# SC01_ProtoBoard_V0_1.net
KiCad netlist of a schematic drawn in EAGLE
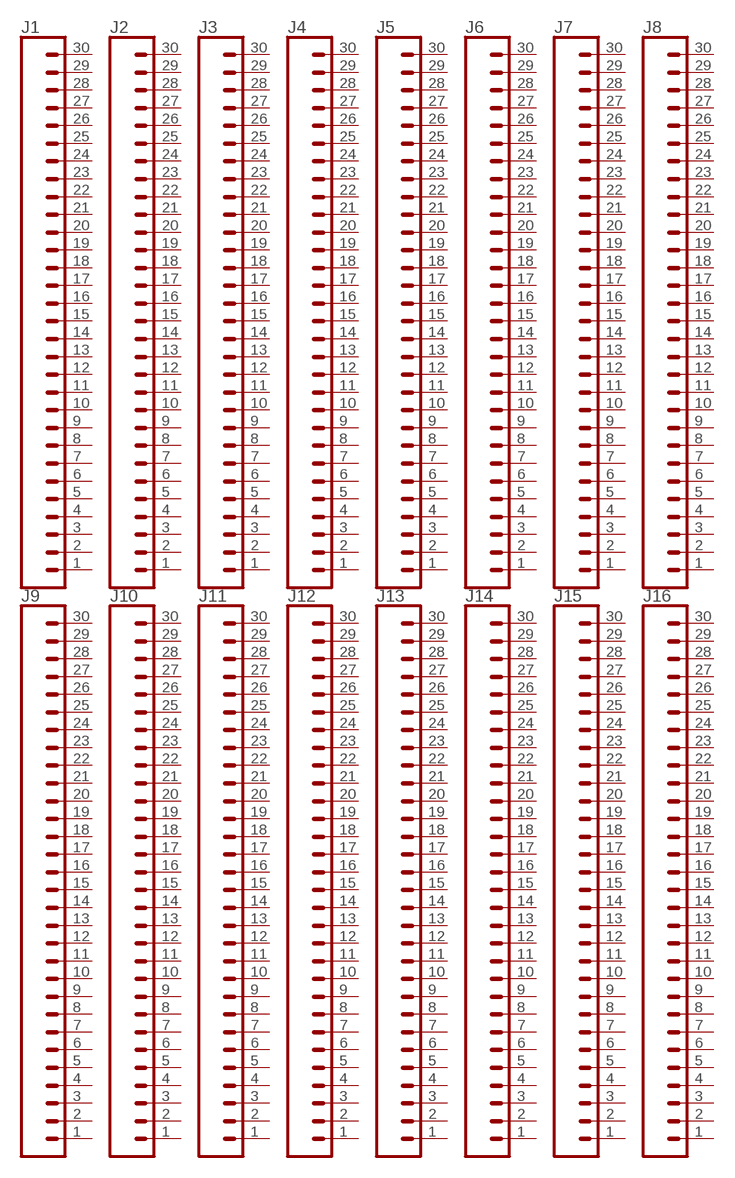
[diagram p0: schematic, sheet 1]
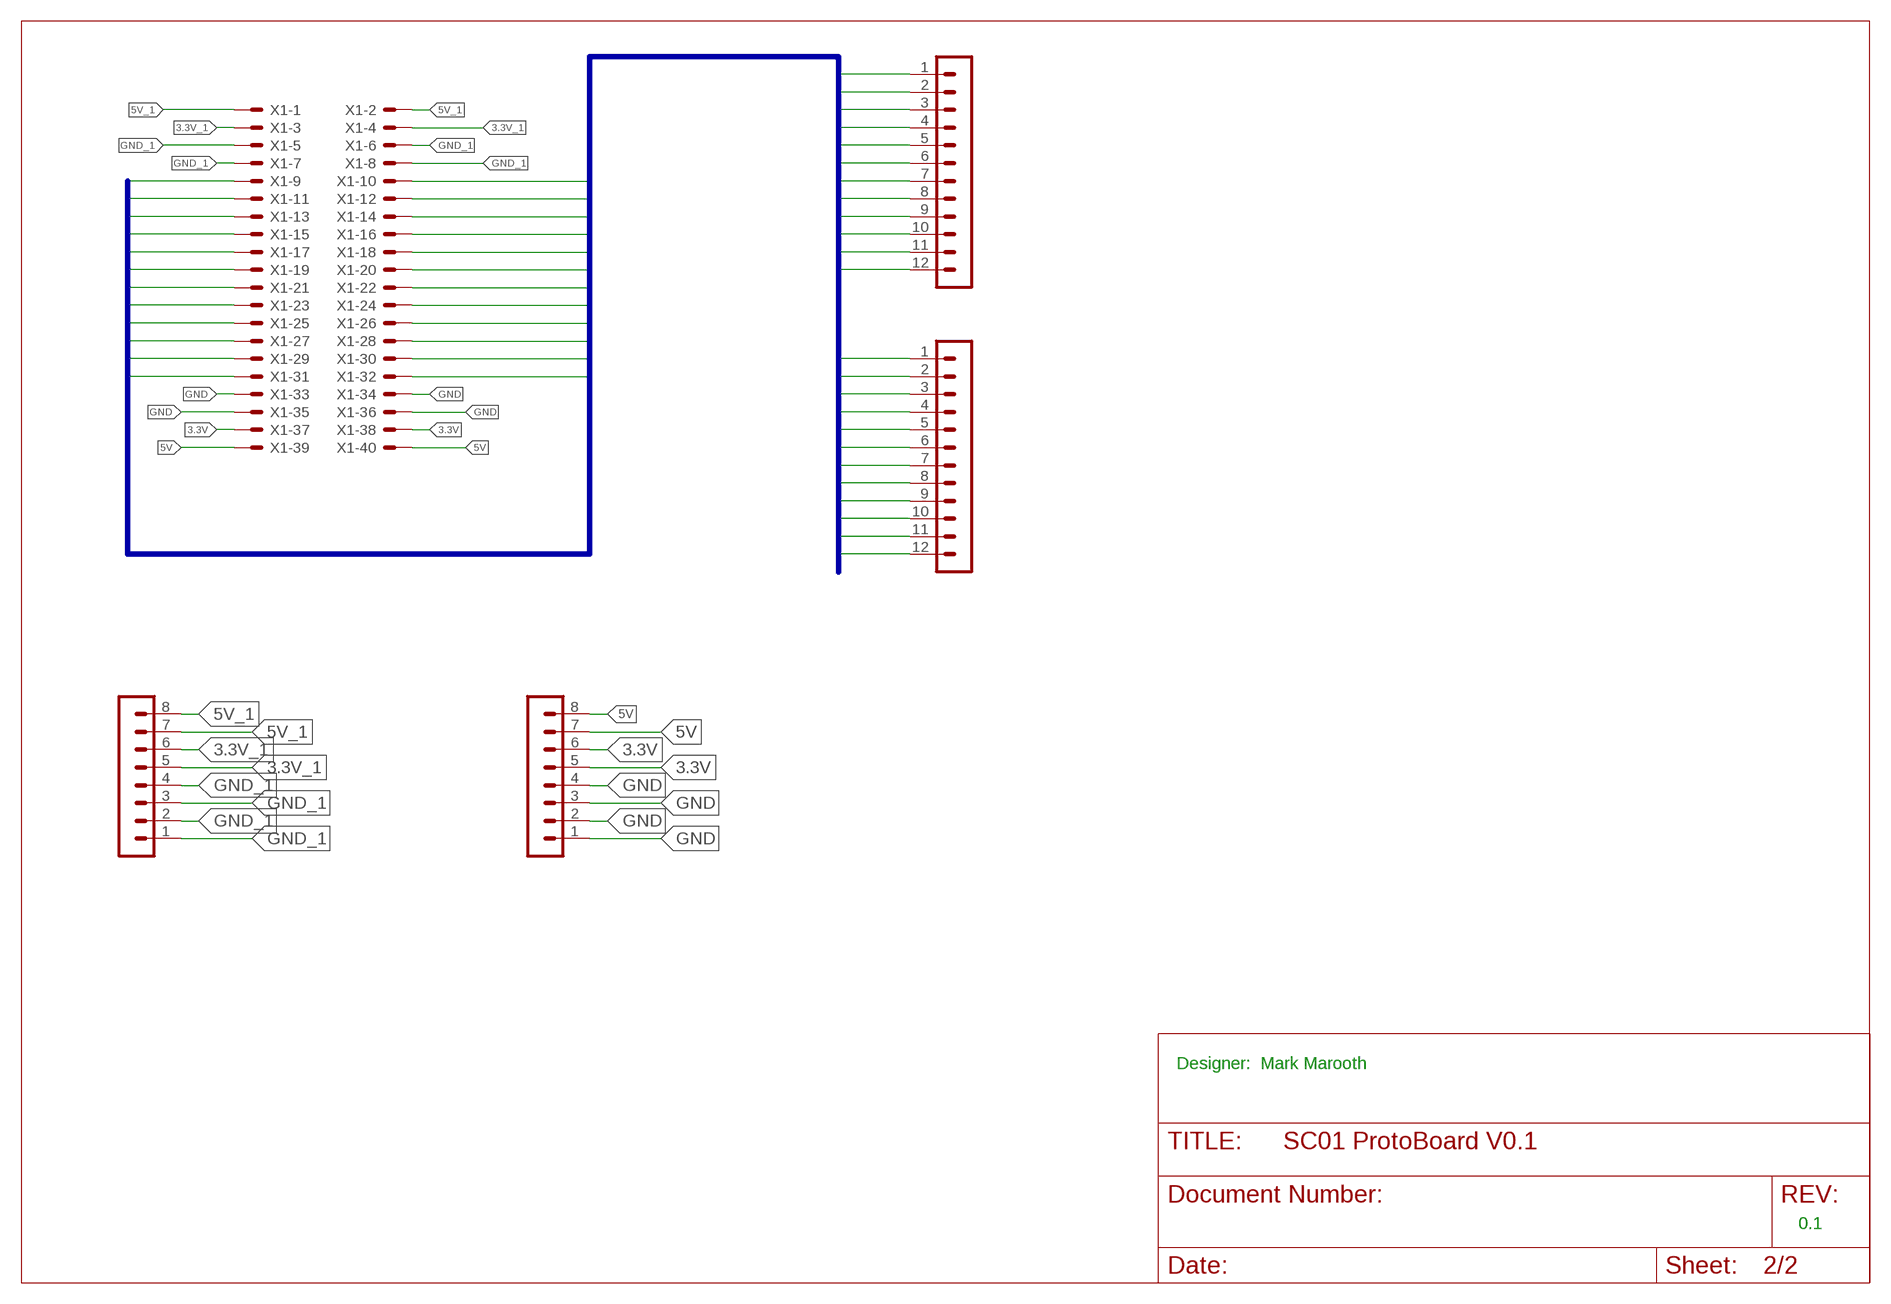
[diagram p1: schematic, sheet 2]

(export (version "E")
  (design (tool "Eeschema 10.0.6"))
  (components
    (comp (ref "J1")
      (value "CONN_30NO_SILK")
      (footprint "eagle-import:1X30_NO_SILK")
      (libsource (lib "eagle-import") (part "CONN_30NO_SILK"))
    )
    (comp (ref "J2")
      (value "CONN_30NO_SILK")
      (footprint "eagle-import:1X30_NO_SILK")
      (libsource (lib "eagle-import") (part "CONN_30NO_SILK"))
    )
    (comp (ref "J3")
      (value "CONN_30NO_SILK")
      (footprint "eagle-import:1X30_NO_SILK")
      (libsource (lib "eagle-import") (part "CONN_30NO_SILK"))
    )
    (comp (ref "J4")
      (value "CONN_30NO_SILK")
      (footprint "eagle-import:1X30_NO_SILK")
      (libsource (lib "eagle-import") (part "CONN_30NO_SILK"))
    )
    (comp (ref "J5")
      (value "CONN_30NO_SILK")
      (footprint "eagle-import:1X30_NO_SILK")
      (libsource (lib "eagle-import") (part "CONN_30NO_SILK"))
    )
    (comp (ref "J6")
      (value "CONN_30NO_SILK")
      (footprint "eagle-import:1X30_NO_SILK")
      (libsource (lib "eagle-import") (part "CONN_30NO_SILK"))
    )
    (comp (ref "J7")
      (value "CONN_30NO_SILK")
      (footprint "eagle-import:1X30_NO_SILK")
      (libsource (lib "eagle-import") (part "CONN_30NO_SILK"))
    )
    (comp (ref "J8")
      (value "CONN_30NO_SILK")
      (footprint "eagle-import:1X30_NO_SILK")
      (libsource (lib "eagle-import") (part "CONN_30NO_SILK"))
    )
    (comp (ref "J9")
      (value "CONN_30NO_SILK")
      (footprint "eagle-import:1X30_NO_SILK")
      (libsource (lib "eagle-import") (part "CONN_30NO_SILK"))
    )
    (comp (ref "J10")
      (value "CONN_30NO_SILK")
      (footprint "eagle-import:1X30_NO_SILK")
      (libsource (lib "eagle-import") (part "CONN_30NO_SILK"))
    )
    (comp (ref "J11")
      (value "CONN_30NO_SILK")
      (footprint "eagle-import:1X30_NO_SILK")
      (libsource (lib "eagle-import") (part "CONN_30NO_SILK"))
    )
    (comp (ref "J12")
      (value "CONN_30NO_SILK")
      (footprint "eagle-import:1X30_NO_SILK")
      (libsource (lib "eagle-import") (part "CONN_30NO_SILK"))
    )
    (comp (ref "J13")
      (value "CONN_30NO_SILK")
      (footprint "eagle-import:1X30_NO_SILK")
      (libsource (lib "eagle-import") (part "CONN_30NO_SILK"))
    )
    (comp (ref "J14")
      (value "CONN_30NO_SILK")
      (footprint "eagle-import:1X30_NO_SILK")
      (libsource (lib "eagle-import") (part "CONN_30NO_SILK"))
    )
    (comp (ref "J15")
      (value "CONN_30NO_SILK")
      (footprint "eagle-import:1X30_NO_SILK")
      (libsource (lib "eagle-import") (part "CONN_30NO_SILK"))
    )
    (comp (ref "J16")
      (value "CONN_30NO_SILK")
      (footprint "eagle-import:1X30_NO_SILK")
      (libsource (lib "eagle-import") (part "CONN_30NO_SILK"))
    )
    (comp (ref "HDR1")
      (value "MA12-1")
      (footprint "eagle-import:MA12-1")
      (libsource (lib "eagle-import") (part "MA12-1"))
    )
    (comp (ref "HDR2")
      (value "MA12-1")
      (footprint "eagle-import:MA12-1")
      (libsource (lib "eagle-import") (part "MA12-1"))
    )
    (comp (ref "HDR3")
      (value "MA08-1")
      (footprint "eagle-import:MA08-1")
      (libsource (lib "eagle-import") (part "MA08-1"))
    )
    (comp (ref "HDR4")
      (value "MA08-1")
      (footprint "eagle-import:MA08-1")
      (libsource (lib "eagle-import") (part "MA08-1"))
    )
    (comp (ref "X1")
      (value "87758-4016")
      (footprint "eagle-import:87758-4016")
      (libsource (lib "eagle-import") (part "87758-4016"))
    )
  )
  (nets
    (net (code "1") (name "3.3V") (class "Default")
      (node (ref "HDR4") (pin "5") (pinfunction "5_5") (pintype "passive"))
      (node (ref "HDR4") (pin "6") (pinfunction "6_6") (pintype "passive"))
      (node (ref "X1") (pin "37") (pinfunction "S_37") (pintype "passive"))
      (node (ref "X1") (pin "38") (pinfunction "S_38") (pintype "passive"))
    )
    (net (code "2") (name "3.3V_1") (class "Default")
      (node (ref "HDR3") (pin "5") (pinfunction "5_5") (pintype "passive"))
      (node (ref "HDR3") (pin "6") (pinfunction "6_6") (pintype "passive"))
      (node (ref "X1") (pin "3") (pinfunction "S_3") (pintype "passive"))
      (node (ref "X1") (pin "4") (pinfunction "S_4") (pintype "passive"))
    )
    (net (code "3") (name "5V") (class "Default")
      (node (ref "HDR4") (pin "7") (pinfunction "7_7") (pintype "passive"))
      (node (ref "HDR4") (pin "8") (pinfunction "8_8") (pintype "passive"))
      (node (ref "X1") (pin "39") (pinfunction "S_39") (pintype "passive"))
      (node (ref "X1") (pin "40") (pinfunction "S_40") (pintype "passive"))
    )
    (net (code "4") (name "5V_1") (class "Default")
      (node (ref "HDR3") (pin "7") (pinfunction "7_7") (pintype "passive"))
      (node (ref "HDR3") (pin "8") (pinfunction "8_8") (pintype "passive"))
      (node (ref "X1") (pin "1") (pinfunction "S_1") (pintype "passive"))
      (node (ref "X1") (pin "2") (pinfunction "S_2") (pintype "passive"))
    )
    (net (code "5") (name "GND") (class "Default")
      (node (ref "HDR4") (pin "1") (pinfunction "1_1") (pintype "passive"))
      (node (ref "HDR4") (pin "2") (pinfunction "2_2") (pintype "passive"))
      (node (ref "HDR4") (pin "3") (pinfunction "3_3") (pintype "passive"))
      (node (ref "HDR4") (pin "4") (pinfunction "4_4") (pintype "passive"))
      (node (ref "X1") (pin "33") (pinfunction "S_33") (pintype "passive"))
      (node (ref "X1") (pin "34") (pinfunction "S_34") (pintype "passive"))
      (node (ref "X1") (pin "35") (pinfunction "S_35") (pintype "passive"))
      (node (ref "X1") (pin "36") (pinfunction "S_36") (pintype "passive"))
    )
    (net (code "6") (name "GND_1") (class "Default")
      (node (ref "HDR3") (pin "1") (pinfunction "1_1") (pintype "passive"))
      (node (ref "HDR3") (pin "2") (pinfunction "2_2") (pintype "passive"))
      (node (ref "HDR3") (pin "3") (pinfunction "3_3") (pintype "passive"))
      (node (ref "HDR3") (pin "4") (pinfunction "4_4") (pintype "passive"))
      (node (ref "X1") (pin "5") (pinfunction "S_5") (pintype "passive"))
      (node (ref "X1") (pin "6") (pinfunction "S_6") (pintype "passive"))
      (node (ref "X1") (pin "7") (pinfunction "S_7") (pintype "passive"))
      (node (ref "X1") (pin "8") (pinfunction "S_8") (pintype "passive"))
    )
    (net (code "7") (name "PHEADER9") (class "Default")
      (node (ref "HDR1") (pin "1") (pinfunction "1_1") (pintype "passive"))
      (node (ref "X1") (pin "9") (pinfunction "S_9") (pintype "passive"))
    )
    (net (code "8") (name "PHEADER10") (class "Default")
      (node (ref "HDR1") (pin "2") (pinfunction "2_2") (pintype "passive"))
      (node (ref "X1") (pin "10") (pinfunction "S_10") (pintype "passive"))
    )
    (net (code "9") (name "PHEADER11") (class "Default")
      (node (ref "HDR1") (pin "3") (pinfunction "3_3") (pintype "passive"))
      (node (ref "X1") (pin "11") (pinfunction "S_11") (pintype "passive"))
    )
    (net (code "10") (name "PHEADER12") (class "Default")
      (node (ref "HDR1") (pin "4") (pinfunction "4_4") (pintype "passive"))
      (node (ref "X1") (pin "12") (pinfunction "S_12") (pintype "passive"))
    )
    (net (code "11") (name "PHEADER13") (class "Default")
      (node (ref "HDR1") (pin "5") (pinfunction "5_5") (pintype "passive"))
      (node (ref "X1") (pin "13") (pinfunction "S_13") (pintype "passive"))
    )
    (net (code "12") (name "PHEADER14") (class "Default")
      (node (ref "HDR1") (pin "6") (pinfunction "6_6") (pintype "passive"))
      (node (ref "X1") (pin "14") (pinfunction "S_14") (pintype "passive"))
    )
    (net (code "13") (name "PHEADER15") (class "Default")
      (node (ref "HDR1") (pin "7") (pinfunction "7_7") (pintype "passive"))
      (node (ref "X1") (pin "15") (pinfunction "S_15") (pintype "passive"))
    )
    (net (code "14") (name "PHEADER16") (class "Default")
      (node (ref "HDR1") (pin "8") (pinfunction "8_8") (pintype "passive"))
      (node (ref "X1") (pin "16") (pinfunction "S_16") (pintype "passive"))
    )
    (net (code "15") (name "PHEADER17") (class "Default")
      (node (ref "HDR1") (pin "9") (pinfunction "9_9") (pintype "passive"))
      (node (ref "X1") (pin "17") (pinfunction "S_17") (pintype "passive"))
    )
    (net (code "16") (name "PHEADER18") (class "Default")
      (node (ref "HDR1") (pin "10") (pinfunction "10_10") (pintype "passive"))
      (node (ref "X1") (pin "18") (pinfunction "S_18") (pintype "passive"))
    )
    (net (code "17") (name "PHEADER19") (class "Default")
      (node (ref "HDR1") (pin "11") (pinfunction "11_11") (pintype "passive"))
      (node (ref "X1") (pin "19") (pinfunction "S_19") (pintype "passive"))
    )
    (net (code "18") (name "PHEADER20") (class "Default")
      (node (ref "HDR1") (pin "12") (pinfunction "12_12") (pintype "passive"))
      (node (ref "X1") (pin "20") (pinfunction "S_20") (pintype "passive"))
    )
    (net (code "19") (name "PHEADER21") (class "Default")
      (node (ref "HDR2") (pin "1") (pinfunction "1_1") (pintype "passive"))
      (node (ref "X1") (pin "21") (pinfunction "S_21") (pintype "passive"))
    )
    (net (code "20") (name "PHEADER22") (class "Default")
      (node (ref "HDR2") (pin "2") (pinfunction "2_2") (pintype "passive"))
      (node (ref "X1") (pin "22") (pinfunction "S_22") (pintype "passive"))
    )
    (net (code "21") (name "PHEADER23") (class "Default")
      (node (ref "HDR2") (pin "3") (pinfunction "3_3") (pintype "passive"))
      (node (ref "X1") (pin "23") (pinfunction "S_23") (pintype "passive"))
    )
    (net (code "22") (name "PHEADER24") (class "Default")
      (node (ref "HDR2") (pin "4") (pinfunction "4_4") (pintype "passive"))
      (node (ref "X1") (pin "24") (pinfunction "S_24") (pintype "passive"))
    )
    (net (code "23") (name "PHEADER25") (class "Default")
      (node (ref "HDR2") (pin "5") (pinfunction "5_5") (pintype "passive"))
      (node (ref "X1") (pin "25") (pinfunction "S_25") (pintype "passive"))
    )
    (net (code "24") (name "PHEADER26") (class "Default")
      (node (ref "HDR2") (pin "6") (pinfunction "6_6") (pintype "passive"))
      (node (ref "X1") (pin "26") (pinfunction "S_26") (pintype "passive"))
    )
    (net (code "25") (name "PHEADER27") (class "Default")
      (node (ref "HDR2") (pin "7") (pinfunction "7_7") (pintype "passive"))
      (node (ref "X1") (pin "27") (pinfunction "S_27") (pintype "passive"))
    )
    (net (code "26") (name "PHEADER28") (class "Default")
      (node (ref "HDR2") (pin "8") (pinfunction "8_8") (pintype "passive"))
      (node (ref "X1") (pin "28") (pinfunction "S_28") (pintype "passive"))
    )
    (net (code "27") (name "PHEADER29") (class "Default")
      (node (ref "HDR2") (pin "9") (pinfunction "9_9") (pintype "passive"))
      (node (ref "X1") (pin "29") (pinfunction "S_29") (pintype "passive"))
    )
    (net (code "28") (name "PHEADER30") (class "Default")
      (node (ref "HDR2") (pin "10") (pinfunction "10_10") (pintype "passive"))
      (node (ref "X1") (pin "30") (pinfunction "S_30") (pintype "passive"))
    )
    (net (code "29") (name "PHEADER31") (class "Default")
      (node (ref "HDR2") (pin "11") (pinfunction "11_11") (pintype "passive"))
      (node (ref "X1") (pin "31") (pinfunction "S_31") (pintype "passive"))
    )
    (net (code "30") (name "PHEADER32") (class "Default")
      (node (ref "HDR2") (pin "12") (pinfunction "12_12") (pintype "passive"))
      (node (ref "X1") (pin "32") (pinfunction "S_32") (pintype "passive"))
    )
    (net (code "31") (name "unconnected-(J1-Pad1)") (class "Default")
      (node (ref "J1") (pin "1") (pinfunction "1_1") (pintype "passive"))
    )
    (net (code "32") (name "unconnected-(J1-Pad2)") (class "Default")
      (node (ref "J1") (pin "2") (pinfunction "2_2") (pintype "passive"))
    )
    (net (code "33") (name "unconnected-(J1-Pad3)") (class "Default")
      (node (ref "J1") (pin "3") (pinfunction "3_3") (pintype "passive"))
    )
    (net (code "34") (name "unconnected-(J1-Pad4)") (class "Default")
      (node (ref "J1") (pin "4") (pinfunction "4_4") (pintype "passive"))
    )
    (net (code "35") (name "unconnected-(J1-Pad5)") (class "Default")
      (node (ref "J1") (pin "5") (pinfunction "5_5") (pintype "passive"))
    )
    (net (code "36") (name "unconnected-(J1-Pad6)") (class "Default")
      (node (ref "J1") (pin "6") (pinfunction "6_6") (pintype "passive"))
    )
    (net (code "37") (name "unconnected-(J1-Pad7)") (class "Default")
      (node (ref "J1") (pin "7") (pinfunction "7_7") (pintype "passive"))
    )
    (net (code "38") (name "unconnected-(J1-Pad8)") (class "Default")
      (node (ref "J1") (pin "8") (pinfunction "8_8") (pintype "passive"))
    )
    (net (code "39") (name "unconnected-(J1-Pad9)") (class "Default")
      (node (ref "J1") (pin "9") (pinfunction "9_9") (pintype "passive"))
    )
    (net (code "40") (name "unconnected-(J1-Pad10)") (class "Default")
      (node (ref "J1") (pin "10") (pinfunction "10_10") (pintype "passive"))
    )
    (net (code "41") (name "unconnected-(J1-Pad11)") (class "Default")
      (node (ref "J1") (pin "11") (pinfunction "11_11") (pintype "passive"))
    )
    (net (code "42") (name "unconnected-(J1-Pad12)") (class "Default")
      (node (ref "J1") (pin "12") (pinfunction "12_12") (pintype "passive"))
    )
    (net (code "43") (name "unconnected-(J1-Pad13)") (class "Default")
      (node (ref "J1") (pin "13") (pinfunction "13_13") (pintype "passive"))
    )
    (net (code "44") (name "unconnected-(J1-Pad14)") (class "Default")
      (node (ref "J1") (pin "14") (pinfunction "14_14") (pintype "passive"))
    )
    (net (code "45") (name "unconnected-(J1-Pad15)") (class "Default")
      (node (ref "J1") (pin "15") (pinfunction "15_15") (pintype "passive"))
    )
    (net (code "46") (name "unconnected-(J1-Pad16)") (class "Default")
      (node (ref "J1") (pin "16") (pinfunction "16_16") (pintype "passive"))
    )
    (net (code "47") (name "unconnected-(J1-Pad17)") (class "Default")
      (node (ref "J1") (pin "17") (pinfunction "17_17") (pintype "passive"))
    )
    (net (code "48") (name "unconnected-(J1-Pad18)") (class "Default")
      (node (ref "J1") (pin "18") (pinfunction "18_18") (pintype "passive"))
    )
    (net (code "49") (name "unconnected-(J1-Pad19)") (class "Default")
      (node (ref "J1") (pin "19") (pinfunction "19_19") (pintype "passive"))
    )
    (net (code "50") (name "unconnected-(J1-Pad20)") (class "Default")
      (node (ref "J1") (pin "20") (pinfunction "20_20") (pintype "passive"))
    )
    (net (code "51") (name "unconnected-(J1-Pad21)") (class "Default")
      (node (ref "J1") (pin "21") (pinfunction "21_21") (pintype "passive"))
    )
    (net (code "52") (name "unconnected-(J1-Pad22)") (class "Default")
      (node (ref "J1") (pin "22") (pinfunction "22_22") (pintype "passive"))
    )
    (net (code "53") (name "unconnected-(J1-Pad23)") (class "Default")
      (node (ref "J1") (pin "23") (pinfunction "23_23") (pintype "passive"))
    )
    (net (code "54") (name "unconnected-(J1-Pad24)") (class "Default")
      (node (ref "J1") (pin "24") (pinfunction "24_24") (pintype "passive"))
    )
    (net (code "55") (name "unconnected-(J1-Pad25)") (class "Default")
      (node (ref "J1") (pin "25") (pinfunction "25_25") (pintype "passive"))
    )
    (net (code "56") (name "unconnected-(J1-Pad26)") (class "Default")
      (node (ref "J1") (pin "26") (pinfunction "26_26") (pintype "passive"))
    )
    (net (code "57") (name "unconnected-(J1-Pad27)") (class "Default")
      (node (ref "J1") (pin "27") (pinfunction "27_27") (pintype "passive"))
    )
    (net (code "58") (name "unconnected-(J1-Pad28)") (class "Default")
      (node (ref "J1") (pin "28") (pinfunction "28_28") (pintype "passive"))
    )
    (net (code "59") (name "unconnected-(J1-Pad29)") (class "Default")
      (node (ref "J1") (pin "29") (pinfunction "29_29") (pintype "passive"))
    )
    (net (code "60") (name "unconnected-(J1-Pad30)") (class "Default")
      (node (ref "J1") (pin "30") (pinfunction "30_30") (pintype "passive"))
    )
    (net (code "61") (name "unconnected-(J2-Pad1)") (class "Default")
      (node (ref "J2") (pin "1") (pinfunction "1_1") (pintype "passive"))
    )
    (net (code "62") (name "unconnected-(J2-Pad2)") (class "Default")
      (node (ref "J2") (pin "2") (pinfunction "2_2") (pintype "passive"))
    )
    (net (code "63") (name "unconnected-(J2-Pad3)") (class "Default")
      (node (ref "J2") (pin "3") (pinfunction "3_3") (pintype "passive"))
    )
    (net (code "64") (name "unconnected-(J2-Pad4)") (class "Default")
      (node (ref "J2") (pin "4") (pinfunction "4_4") (pintype "passive"))
    )
    (net (code "65") (name "unconnected-(J2-Pad5)") (class "Default")
      (node (ref "J2") (pin "5") (pinfunction "5_5") (pintype "passive"))
    )
    (net (code "66") (name "unconnected-(J2-Pad6)") (class "Default")
      (node (ref "J2") (pin "6") (pinfunction "6_6") (pintype "passive"))
    )
    (net (code "67") (name "unconnected-(J2-Pad7)") (class "Default")
      (node (ref "J2") (pin "7") (pinfunction "7_7") (pintype "passive"))
    )
    (net (code "68") (name "unconnected-(J2-Pad8)") (class "Default")
      (node (ref "J2") (pin "8") (pinfunction "8_8") (pintype "passive"))
    )
    (net (code "69") (name "unconnected-(J2-Pad9)") (class "Default")
      (node (ref "J2") (pin "9") (pinfunction "9_9") (pintype "passive"))
    )
    (net (code "70") (name "unconnected-(J2-Pad10)") (class "Default")
      (node (ref "J2") (pin "10") (pinfunction "10_10") (pintype "passive"))
    )
    (net (code "71") (name "unconnected-(J2-Pad11)") (class "Default")
      (node (ref "J2") (pin "11") (pinfunction "11_11") (pintype "passive"))
    )
    (net (code "72") (name "unconnected-(J2-Pad12)") (class "Default")
      (node (ref "J2") (pin "12") (pinfunction "12_12") (pintype "passive"))
    )
    (net (code "73") (name "unconnected-(J2-Pad13)") (class "Default")
      (node (ref "J2") (pin "13") (pinfunction "13_13") (pintype "passive"))
    )
    (net (code "74") (name "unconnected-(J2-Pad14)") (class "Default")
      (node (ref "J2") (pin "14") (pinfunction "14_14") (pintype "passive"))
    )
    (net (code "75") (name "unconnected-(J2-Pad15)") (class "Default")
      (node (ref "J2") (pin "15") (pinfunction "15_15") (pintype "passive"))
    )
    (net (code "76") (name "unconnected-(J2-Pad16)") (class "Default")
      (node (ref "J2") (pin "16") (pinfunction "16_16") (pintype "passive"))
    )
    (net (code "77") (name "unconnected-(J2-Pad17)") (class "Default")
      (node (ref "J2") (pin "17") (pinfunction "17_17") (pintype "passive"))
    )
    (net (code "78") (name "unconnected-(J2-Pad18)") (class "Default")
      (node (ref "J2") (pin "18") (pinfunction "18_18") (pintype "passive"))
    )
    (net (code "79") (name "unconnected-(J2-Pad19)") (class "Default")
      (node (ref "J2") (pin "19") (pinfunction "19_19") (pintype "passive"))
    )
    (net (code "80") (name "unconnected-(J2-Pad20)") (class "Default")
      (node (ref "J2") (pin "20") (pinfunction "20_20") (pintype "passive"))
    )
    (net (code "81") (name "unconnected-(J2-Pad21)") (class "Default")
      (node (ref "J2") (pin "21") (pinfunction "21_21") (pintype "passive"))
    )
    (net (code "82") (name "unconnected-(J2-Pad22)") (class "Default")
      (node (ref "J2") (pin "22") (pinfunction "22_22") (pintype "passive"))
    )
    (net (code "83") (name "unconnected-(J2-Pad23)") (class "Default")
      (node (ref "J2") (pin "23") (pinfunction "23_23") (pintype "passive"))
    )
    (net (code "84") (name "unconnected-(J2-Pad24)") (class "Default")
      (node (ref "J2") (pin "24") (pinfunction "24_24") (pintype "passive"))
    )
    (net (code "85") (name "unconnected-(J2-Pad25)") (class "Default")
      (node (ref "J2") (pin "25") (pinfunction "25_25") (pintype "passive"))
    )
    (net (code "86") (name "unconnected-(J2-Pad26)") (class "Default")
      (node (ref "J2") (pin "26") (pinfunction "26_26") (pintype "passive"))
    )
    (net (code "87") (name "unconnected-(J2-Pad27)") (class "Default")
      (node (ref "J2") (pin "27") (pinfunction "27_27") (pintype "passive"))
    )
    (net (code "88") (name "unconnected-(J2-Pad28)") (class "Default")
      (node (ref "J2") (pin "28") (pinfunction "28_28") (pintype "passive"))
    )
    (net (code "89") (name "unconnected-(J2-Pad29)") (class "Default")
      (node (ref "J2") (pin "29") (pinfunction "29_29") (pintype "passive"))
    )
    (net (code "90") (name "unconnected-(J2-Pad30)") (class "Default")
      (node (ref "J2") (pin "30") (pinfunction "30_30") (pintype "passive"))
    )
    (net (code "91") (name "unconnected-(J3-Pad1)") (class "Default")
      (node (ref "J3") (pin "1") (pinfunction "1_1") (pintype "passive"))
    )
    (net (code "92") (name "unconnected-(J3-Pad2)") (class "Default")
      (node (ref "J3") (pin "2") (pinfunction "2_2") (pintype "passive"))
    )
    (net (code "93") (name "unconnected-(J3-Pad3)") (class "Default")
      (node (ref "J3") (pin "3") (pinfunction "3_3") (pintype "passive"))
    )
    (net (code "94") (name "unconnected-(J3-Pad4)") (class "Default")
      (node (ref "J3") (pin "4") (pinfunction "4_4") (pintype "passive"))
    )
    (net (code "95") (name "unconnected-(J3-Pad5)") (class "Default")
      (node (ref "J3") (pin "5") (pinfunction "5_5") (pintype "passive"))
    )
    (net (code "96") (name "unconnected-(J3-Pad6)") (class "Default")
      (node (ref "J3") (pin "6") (pinfunction "6_6") (pintype "passive"))
    )
    (net (code "97") (name "unconnected-(J3-Pad7)") (class "Default")
      (node (ref "J3") (pin "7") (pinfunction "7_7") (pintype "passive"))
    )
    (net (code "98") (name "unconnected-(J3-Pad8)") (class "Default")
      (node (ref "J3") (pin "8") (pinfunction "8_8") (pintype "passive"))
    )
    (net (code "99") (name "unconnected-(J3-Pad9)") (class "Default")
      (node (ref "J3") (pin "9") (pinfunction "9_9") (pintype "passive"))
    )
    (net (code "100") (name "unconnected-(J3-Pad10)") (class "Default")
      (node (ref "J3") (pin "10") (pinfunction "10_10") (pintype "passive"))
    )
    (net (code "101") (name "unconnected-(J3-Pad11)") (class "Default")
      (node (ref "J3") (pin "11") (pinfunction "11_11") (pintype "passive"))
    )
    (net (code "102") (name "unconnected-(J3-Pad12)") (class "Default")
      (node (ref "J3") (pin "12") (pinfunction "12_12") (pintype "passive"))
    )
    (net (code "103") (name "unconnected-(J3-Pad13)") (class "Default")
      (node (ref "J3") (pin "13") (pinfunction "13_13") (pintype "passive"))
    )
    (net (code "104") (name "unconnected-(J3-Pad14)") (class "Default")
      (node (ref "J3") (pin "14") (pinfunction "14_14") (pintype "passive"))
    )
    (net (code "105") (name "unconnected-(J3-Pad15)") (class "Default")
      (node (ref "J3") (pin "15") (pinfunction "15_15") (pintype "passive"))
    )
    (net (code "106") (name "unconnected-(J3-Pad16)") (class "Default")
      (node (ref "J3") (pin "16") (pinfunction "16_16") (pintype "passive"))
    )
    (net (code "107") (name "unconnected-(J3-Pad17)") (class "Default")
      (node (ref "J3") (pin "17") (pinfunction "17_17") (pintype "passive"))
    )
    (net (code "108") (name "unconnected-(J3-Pad18)") (class "Default")
      (node (ref "J3") (pin "18") (pinfunction "18_18") (pintype "passive"))
    )
    (net (code "109") (name "unconnected-(J3-Pad19)") (class "Default")
      (node (ref "J3") (pin "19") (pinfunction "19_19") (pintype "passive"))
    )
    (net (code "110") (name "unconnected-(J3-Pad20)") (class "Default")
      (node (ref "J3") (pin "20") (pinfunction "20_20") (pintype "passive"))
    )
    (net (code "111") (name "unconnected-(J3-Pad21)") (class "Default")
      (node (ref "J3") (pin "21") (pinfunction "21_21") (pintype "passive"))
    )
    (net (code "112") (name "unconnected-(J3-Pad22)") (class "Default")
      (node (ref "J3") (pin "22") (pinfunction "22_22") (pintype "passive"))
    )
    (net (code "113") (name "unconnected-(J3-Pad23)") (class "Default")
      (node (ref "J3") (pin "23") (pinfunction "23_23") (pintype "passive"))
    )
    (net (code "114") (name "unconnected-(J3-Pad24)") (class "Default")
      (node (ref "J3") (pin "24") (pinfunction "24_24") (pintype "passive"))
    )
    (net (code "115") (name "unconnected-(J3-Pad25)") (class "Default")
      (node (ref "J3") (pin "25") (pinfunction "25_25") (pintype "passive"))
    )
    (net (code "116") (name "unconnected-(J3-Pad26)") (class "Default")
      (node (ref "J3") (pin "26") (pinfunction "26_26") (pintype "passive"))
    )
    (net (code "117") (name "unconnected-(J3-Pad27)") (class "Default")
      (node (ref "J3") (pin "27") (pinfunction "27_27") (pintype "passive"))
    )
    (net (code "118") (name "unconnected-(J3-Pad28)") (class "Default")
      (node (ref "J3") (pin "28") (pinfunction "28_28") (pintype "passive"))
    )
    (net (code "119") (name "unconnected-(J3-Pad29)") (class "Default")
      (node (ref "J3") (pin "29") (pinfunction "29_29") (pintype "passive"))
    )
    (net (code "120") (name "unconnected-(J3-Pad30)") (class "Default")
      (node (ref "J3") (pin "30") (pinfunction "30_30") (pintype "passive"))
    )
    (net (code "121") (name "unconnected-(J4-Pad1)") (class "Default")
      (node (ref "J4") (pin "1") (pinfunction "1_1") (pintype "passive"))
    )
    (net (code "122") (name "unconnected-(J4-Pad2)") (class "Default")
      (node (ref "J4") (pin "2") (pinfunction "2_2") (pintype "passive"))
    )
    (net (code "123") (name "unconnected-(J4-Pad3)") (class "Default")
      (node (ref "J4") (pin "3") (pinfunction "3_3") (pintype "passive"))
    )
    (net (code "124") (name "unconnected-(J4-Pad4)") (class "Default")
      (node (ref "J4") (pin "4") (pinfunction "4_4") (pintype "passive"))
    )
    (net (code "125") (name "unconnected-(J4-Pad5)") (class "Default")
      (node (ref "J4") (pin "5") (pinfunction "5_5") (pintype "passive"))
    )
    (net (code "126") (name "unconnected-(J4-Pad6)") (class "Default")
      (node (ref "J4") (pin "6") (pinfunction "6_6") (pintype "passive"))
    )
    (net (code "127") (name "unconnected-(J4-Pad7)") (class "Default")
      (node (ref "J4") (pin "7") (pinfunction "7_7") (pintype "passive"))
    )
    (net (code "128") (name "unconnected-(J4-Pad8)") (class "Default")
      (node (ref "J4") (pin "8") (pinfunction "8_8") (pintype "passive"))
    )
    (net (code "129") (name "unconnected-(J4-Pad9)") (class "Default")
      (node (ref "J4") (pin "9") (pinfunction "9_9") (pintype "passive"))
    )
    (net (code "130") (name "unconnected-(J4-Pad10)") (class "Default")
      (node (ref "J4") (pin "10") (pinfunction "10_10") (pintype "passive"))
    )
    (net (code "131") (name "unconnected-(J4-Pad11)") (class "Default")
      (node (ref "J4") (pin "11") (pinfunction "11_11") (pintype "passive"))
    )
    (net (code "132") (name "unconnected-(J4-Pad12)") (class "Default")
      (node (ref "J4") (pin "12") (pinfunction "12_12") (pintype "passive"))
    )
    (net (code "133") (name "unconnected-(J4-Pad13)") (class "Default")
      (node (ref "J4") (pin "13") (pinfunction "13_13") (pintype "passive"))
    )
    (net (code "134") (name "unconnected-(J4-Pad14)") (class "Default")
      (node (ref "J4") (pin "14") (pinfunction "14_14") (pintype "passive"))
    )
    (net (code "135") (name "unconnected-(J4-Pad15)") (class "Default")
      (node (ref "J4") (pin "15") (pinfunction "15_15") (pintype "passive"))
    )
    (net (code "136") (name "unconnected-(J4-Pad16)") (class "Default")
      (node (ref "J4") (pin "16") (pinfunction "16_16") (pintype "passive"))
    )
    (net (code "137") (name "unconnected-(J4-Pad17)") (class "Default")
      (node (ref "J4") (pin "17") (pinfunction "17_17") (pintype "passive"))
    )
    (net (code "138") (name "unconnected-(J4-Pad18)") (class "Default")
      (node (ref "J4") (pin "18") (pinfunction "18_18") (pintype "passive"))
    )
    (net (code "139") (name "unconnected-(J4-Pad19)") (class "Default")
      (node (ref "J4") (pin "19") (pinfunction "19_19") (pintype "passive"))
    )
    (net (code "140") (name "unconnected-(J4-Pad20)") (class "Default")
      (node (ref "J4") (pin "20") (pinfunction "20_20") (pintype "passive"))
    )
    (net (code "141") (name "unconnected-(J4-Pad21)") (class "Default")
      (node (ref "J4") (pin "21") (pinfunction "21_21") (pintype "passive"))
    )
    (net (code "142") (name "unconnected-(J4-Pad22)") (class "Default")
      (node (ref "J4") (pin "22") (pinfunction "22_22") (pintype "passive"))
    )
    (net (code "143") (name "unconnected-(J4-Pad23)") (class "Default")
      (node (ref "J4") (pin "23") (pinfunction "23_23") (pintype "passive"))
    )
    (net (code "144") (name "unconnected-(J4-Pad24)") (class "Default")
      (node (ref "J4") (pin "24") (pinfunction "24_24") (pintype "passive"))
    )
    (net (code "145") (name "unconnected-(J4-Pad25)") (class "Default")
      (node (ref "J4") (pin "25") (pinfunction "25_25") (pintype "passive"))
    )
    (net (code "146") (name "unconnected-(J4-Pad26)") (class "Default")
      (node (ref "J4") (pin "26") (pinfunction "26_26") (pintype "passive"))
    )
    (net (code "147") (name "unconnected-(J4-Pad27)") (class "Default")
      (node (ref "J4") (pin "27") (pinfunction "27_27") (pintype "passive"))
    )
    (net (code "148") (name "unconnected-(J4-Pad28)") (class "Default")
      (node (ref "J4") (pin "28") (pinfunction "28_28") (pintype "passive"))
    )
    (net (code "149") (name "unconnected-(J4-Pad29)") (class "Default")
      (node (ref "J4") (pin "29") (pinfunction "29_29") (pintype "passive"))
    )
    (net (code "150") (name "unconnected-(J4-Pad30)") (class "Default")
      (node (ref "J4") (pin "30") (pinfunction "30_30") (pintype "passive"))
    )
    (net (code "151") (name "unconnected-(J5-Pad1)") (class "Default")
      (node (ref "J5") (pin "1") (pinfunction "1_1") (pintype "passive"))
    )
    (net (code "152") (name "unconnected-(J5-Pad2)") (class "Default")
      (node (ref "J5") (pin "2") (pinfunction "2_2") (pintype "passive"))
    )
    (net (code "153") (name "unconnected-(J5-Pad3)") (class "Default")
      (node (ref "J5") (pin "3") (pinfunction "3_3") (pintype "passive"))
    )
    (net (code "154") (name "unconnected-(J5-Pad4)") (class "Default")
      (node (ref "J5") (pin "4") (pinfunction "4_4") (pintype "passive"))
    )
    (net (code "155") (name "unconnected-(J5-Pad5)") (class "Default")
      (node (ref "J5") (pin "5") (pinfunction "5_5") (pintype "passive"))
    )
    (net (code "156") (name "unconnected-(J5-Pad6)") (class "Default")
      (node (ref "J5") (pin "6") (pinfunction "6_6") (pintype "passive"))
    )
    (net (code "157") (name "unconnected-(J5-Pad7)") (class "Default")
      (node (ref "J5") (pin "7") (pinfunction "7_7") (pintype "passive"))
    )
    (net (code "158") (name "unconnected-(J5-Pad8)") (class "Default")
      (node (ref "J5") (pin "8") (pinfunction "8_8") (pintype "passive"))
    )
    (net (code "159") (name "unconnected-(J5-Pad9)") (class "Default")
      (node (ref "J5") (pin "9") (pinfunction "9_9") (pintype "passive"))
    )
    (net (code "160") (name "unconnected-(J5-Pad10)") (class "Default")
      (node (ref "J5") (pin "10") (pinfunction "10_10") (pintype "passive"))
    )
    (net (code "161") (name "unconnected-(J5-Pad11)") (class "Default")
      (node (ref "J5") (pin "11") (pinfunction "11_11") (pintype "passive"))
    )
    (net (code "162") (name "unconnected-(J5-Pad12)") (class "Default")
      (node (ref "J5") (pin "12") (pinfunction "12_12") (pintype "passive"))
    )
    (net (code "163") (name "unconnected-(J5-Pad13)") (class "Default")
      (node (ref "J5") (pin "13") (pinfunction "13_13") (pintype "passive"))
    )
    (net (code "164") (name "unconnected-(J5-Pad14)") (class "Default")
      (node (ref "J5") (pin "14") (pinfunction "14_14") (pintype "passive"))
    )
    (net (code "165") (name "unconnected-(J5-Pad15)") (class "Default")
      (node (ref "J5") (pin "15") (pinfunction "15_15") (pintype "passive"))
    )
    (net (code "166") (name "unconnected-(J5-Pad16)") (class "Default")
      (node (ref "J5") (pin "16") (pinfunction "16_16") (pintype "passive"))
    )
    (net (code "167") (name "unconnected-(J5-Pad17)") (class "Default")
      (node (ref "J5") (pin "17") (pinfunction "17_17") (pintype "passive"))
    )
    (net (code "168") (name "unconnected-(J5-Pad18)") (class "Default")
      (node (ref "J5") (pin "18") (pinfunction "18_18") (pintype "passive"))
    )
    (net (code "169") (name "unconnected-(J5-Pad19)") (class "Default")
      (node (ref "J5") (pin "19") (pinfunction "19_19") (pintype "passive"))
    )
    (net (code "170") (name "unconnected-(J5-Pad20)") (class "Default")
      (node (ref "J5") (pin "20") (pinfunction "20_20") (pintype "passive"))
    )
    (net (code "171") (name "unconnected-(J5-Pad21)") (class "Default")
      (node (ref "J5") (pin "21") (pinfunction "21_21") (pintype "passive"))
    )
    (net (code "172") (name "unconnected-(J5-Pad22)") (class "Default")
      (node (ref "J5") (pin "22") (pinfunction "22_22") (pintype "passive"))
    )
    (net (code "173") (name "unconnected-(J5-Pad23)") (class "Default")
      (node (ref "J5") (pin "23") (pinfunction "23_23") (pintype "passive"))
    )
    (net (code "174") (name "unconnected-(J5-Pad24)") (class "Default")
      (node (ref "J5") (pin "24") (pinfunction "24_24") (pintype "passive"))
    )
    (net (code "175") (name "unconnected-(J5-Pad25)") (class "Default")
      (node (ref "J5") (pin "25") (pinfunction "25_25") (pintype "passive"))
    )
    (net (code "176") (name "unconnected-(J5-Pad26)") (class "Default")
      (node (ref "J5") (pin "26") (pinfunction "26_26") (pintype "passive"))
    )
    (net (code "177") (name "unconnected-(J5-Pad27)") (class "Default")
      (node (ref "J5") (pin "27") (pinfunction "27_27") (pintype "passive"))
    )
    (net (code "178") (name "unconnected-(J5-Pad28)") (class "Default")
      (node (ref "J5") (pin "28") (pinfunction "28_28") (pintype "passive"))
    )
    (net (code "179") (name "unconnected-(J5-Pad29)") (class "Default")
      (node (ref "J5") (pin "29") (pinfunction "29_29") (pintype "passive"))
    )
    (net (code "180") (name "unconnected-(J5-Pad30)") (class "Default")
      (node (ref "J5") (pin "30") (pinfunction "30_30") (pintype "passive"))
    )
    (net (code "181") (name "unconnected-(J6-Pad1)") (class "Default")
      (node (ref "J6") (pin "1") (pinfunction "1_1") (pintype "passive"))
    )
    (net (code "182") (name "unconnected-(J6-Pad2)") (class "Default")
      (node (ref "J6") (pin "2") (pinfunction "2_2") (pintype "passive"))
    )
    (net (code "183") (name "unconnected-(J6-Pad3)") (class "Default")
      (node (ref "J6") (pin "3") (pinfunction "3_3") (pintype "passive"))
    )
    (net (code "184") (name "unconnected-(J6-Pad4)") (class "Default")
      (node (ref "J6") (pin "4") (pinfunction "4_4") (pintype "passive"))
    )
    (net (code "185") (name "unconnected-(J6-Pad5)") (class "Default")
      (node (ref "J6") (pin "5") (pinfunction "5_5") (pintype "passive"))
    )
    (net (code "186") (name "unconnected-(J6-Pad6)") (class "Default")
      (node (ref "J6") (pin "6") (pinfunction "6_6") (pintype "passive"))
    )
    (net (code "187") (name "unconnected-(J6-Pad7)") (class "Default")
      (node (ref "J6") (pin "7") (pinfunction "7_7") (pintype "passive"))
    )
    (net (code "188") (name "unconnected-(J6-Pad8)") (class "Default")
      (node (ref "J6") (pin "8") (pinfunction "8_8") (pintype "passive"))
    )
    (net (code "189") (name "unconnected-(J6-Pad9)") (class "Default")
      (node (ref "J6") (pin "9") (pinfunction "9_9") (pintype "passive"))
    )
    (net (code "190") (name "unconnected-(J6-Pad10)") (class "Default")
      (node (ref "J6") (pin "10") (pinfunction "10_10") (pintype "passive"))
    )
    (net (code "191") (name "unconnected-(J6-Pad11)") (class "Default")
      (node (ref "J6") (pin "11") (pinfunction "11_11") (pintype "passive"))
    )
    (net (code "192") (name "unconnected-(J6-Pad12)") (class "Default")
      (node (ref "J6") (pin "12") (pinfunction "12_12") (pintype "passive"))
    )
    (net (code "193") (name "unconnected-(J6-Pad13)") (class "Default")
      (node (ref "J6") (pin "13") (pinfunction "13_13") (pintype "passive"))
    )
    (net (code "194") (name "unconnected-(J6-Pad14)") (class "Default")
      (node (ref "J6") (pin "14") (pinfunction "14_14") (pintype "passive"))
    )
    (net (code "195") (name "unconnected-(J6-Pad15)") (class "Default")
      (node (ref "J6") (pin "15") (pinfunction "15_15") (pintype "passive"))
    )
    (net (code "196") (name "unconnected-(J6-Pad16)") (class "Default")
      (node (ref "J6") (pin "16") (pinfunction "16_16") (pintype "passive"))
    )
    (net (code "197") (name "unconnected-(J6-Pad17)") (class "Default")
      (node (ref "J6") (pin "17") (pinfunction "17_17") (pintype "passive"))
    )
    (net (code "198") (name "unconnected-(J6-Pad18)") (class "Default")
      (node (ref "J6") (pin "18") (pinfunction "18_18") (pintype "passive"))
    )
    (net (code "199") (name "unconnected-(J6-Pad19)") (class "Default")
      (node (ref "J6") (pin "19") (pinfunction "19_19") (pintype "passive"))
    )
    (net (code "200") (name "unconnected-(J6-Pad20)") (class "Default")
      (node (ref "J6") (pin "20") (pinfunction "20_20") (pintype "passive"))
    )
    (net (code "201") (name "unconnected-(J6-Pad21)") (class "Default")
      (node (ref "J6") (pin "21") (pinfunction "21_21") (pintype "passive"))
    )
    (net (code "202") (name "unconnected-(J6-Pad22)") (class "Default")
      (node (ref "J6") (pin "22") (pinfunction "22_22") (pintype "passive"))
    )
    (net (code "203") (name "unconnected-(J6-Pad23)") (class "Default")
      (node (ref "J6") (pin "23") (pinfunction "23_23") (pintype "passive"))
    )
    (net (code "204") (name "unconnected-(J6-Pad24)") (class "Default")
      (node (ref "J6") (pin "24") (pinfunction "24_24") (pintype "passive"))
    )
    (net (code "205") (name "unconnected-(J6-Pad25)") (class "Default")
      (node (ref "J6") (pin "25") (pinfunction "25_25") (pintype "passive"))
    )
    (net (code "206") (name "unconnected-(J6-Pad26)") (class "Default")
      (node (ref "J6") (pin "26") (pinfunction "26_26") (pintype "passive"))
    )
    (net (code "207") (name "unconnected-(J6-Pad27)") (class "Default")
      (node (ref "J6") (pin "27") (pinfunction "27_27") (pintype "passive"))
    )
    (net (code "208") (name "unconnected-(J6-Pad28)") (class "Default")
      (node (ref "J6") (pin "28") (pinfunction "28_28") (pintype "passive"))
    )
    (net (code "209") (name "unconnected-(J6-Pad29)") (class "Default")
      (node (ref "J6") (pin "29") (pinfunction "29_29") (pintype "passive"))
    )
    (net (code "210") (name "unconnected-(J6-Pad30)") (class "Default")
      (node (ref "J6") (pin "30") (pinfunction "30_30") (pintype "passive"))
    )
    (net (code "211") (name "unconnected-(J7-Pad1)") (class "Default")
      (node (ref "J7") (pin "1") (pinfunction "1_1") (pintype "passive"))
    )
    (net (code "212") (name "unconnected-(J7-Pad2)") (class "Default")
      (node (ref "J7") (pin "2") (pinfunction "2_2") (pintype "passive"))
    )
    (net (code "213") (name "unconnected-(J7-Pad3)") (class "Default")
      (node (ref "J7") (pin "3") (pinfunction "3_3") (pintype "passive"))
    )
    (net (code "214") (name "unconnected-(J7-Pad4)") (class "Default")
      (node (ref "J7") (pin "4") (pinfunction "4_4") (pintype "passive"))
    )
    (net (code "215") (name "unconnected-(J7-Pad5)") (class "Default")
      (node (ref "J7") (pin "5") (pinfunction "5_5") (pintype "passive"))
    )
    (net (code "216") (name "unconnected-(J7-Pad6)") (class "Default")
      (node (ref "J7") (pin "6") (pinfunction "6_6") (pintype "passive"))
    )
    (net (code "217") (name "unconnected-(J7-Pad7)") (class "Default")
      (node (ref "J7") (pin "7") (pinfunction "7_7") (pintype "passive"))
    )
    (net (code "218") (name "unconnected-(J7-Pad8)") (class "Default")
      (node (ref "J7") (pin "8") (pinfunction "8_8") (pintype "passive"))
    )
    (net (code "219") (name "unconnected-(J7-Pad9)") (class "Default")
      (node (ref "J7") (pin "9") (pinfunction "9_9") (pintype "passive"))
    )
    (net (code "220") (name "unconnected-(J7-Pad10)") (class "Default")
      (node (ref "J7") (pin "10") (pinfunction "10_10") (pintype "passive"))
    )
    (net (code "221") (name "unconnected-(J7-Pad11)") (class "Default")
      (node (ref "J7") (pin "11") (pinfunction "11_11") (pintype "passive"))
    )
    (net (code "222") (name "unconnected-(J7-Pad12)") (class "Default")
      (node (ref "J7") (pin "12") (pinfunction "12_12") (pintype "passive"))
    )
    (net (code "223") (name "unconnected-(J7-Pad13)") (class "Default")
      (node (ref "J7") (pin "13") (pinfunction "13_13") (pintype "passive"))
    )
    (net (code "224") (name "unconnected-(J7-Pad14)") (class "Default")
      (node (ref "J7") (pin "14") (pinfunction "14_14") (pintype "passive"))
    )
    (net (code "225") (name "unconnected-(J7-Pad15)") (class "Default")
      (node (ref "J7") (pin "15") (pinfunction "15_15") (pintype "passive"))
    )
    (net (code "226") (name "unconnected-(J7-Pad16)") (class "Default")
      (node (ref "J7") (pin "16") (pinfunction "16_16") (pintype "passive"))
    )
    (net (code "227") (name "unconnected-(J7-Pad17)") (class "Default")
      (node (ref "J7") (pin "17") (pinfunction "17_17") (pintype "passive"))
    )
    (net (code "228") (name "unconnected-(J7-Pad18)") (class "Default")
      (node (ref "J7") (pin "18") (pinfunction "18_18") (pintype "passive"))
    )
    (net (code "229") (name "unconnected-(J7-Pad19)") (class "Default")
      (node (ref "J7") (pin "19") (pinfunction "19_19") (pintype "passive"))
    )
    (net (code "230") (name "unconnected-(J7-Pad20)") (class "Default")
      (node (ref "J7") (pin "20") (pinfunction "20_20") (pintype "passive"))
    )
    (net (code "231") (name "unconnected-(J7-Pad21)") (class "Default")
      (node (ref "J7") (pin "21") (pinfunction "21_21") (pintype "passive"))
    )
    (net (code "232") (name "unconnected-(J7-Pad22)") (class "Default")
      (node (ref "J7") (pin "22") (pinfunction "22_22") (pintype "passive"))
    )
    (net (code "233") (name "unconnected-(J7-Pad23)") (class "Default")
      (node (ref "J7") (pin "23") (pinfunction "23_23") (pintype "passive"))
    )
    (net (code "234") (name "unconnected-(J7-Pad24)") (class "Default")
      (node (ref "J7") (pin "24") (pinfunction "24_24") (pintype "passive"))
    )
    (net (code "235") (name "unconnected-(J7-Pad25)") (class "Default")
      (node (ref "J7") (pin "25") (pinfunction "25_25") (pintype "passive"))
    )
    (net (code "236") (name "unconnected-(J7-Pad26)") (class "Default")
      (node (ref "J7") (pin "26") (pinfunction "26_26") (pintype "passive"))
    )
    (net (code "237") (name "unconnected-(J7-Pad27)") (class "Default")
      (node (ref "J7") (pin "27") (pinfunction "27_27") (pintype "passive"))
    )
    (net (code "238") (name "unconnected-(J7-Pad28)") (class "Default")
      (node (ref "J7") (pin "28") (pinfunction "28_28") (pintype "passive"))
    )
    (net (code "239") (name "unconnected-(J7-Pad29)") (class "Default")
      (node (ref "J7") (pin "29") (pinfunction "29_29") (pintype "passive"))
    )
    (net (code "240") (name "unconnected-(J7-Pad30)") (class "Default")
      (node (ref "J7") (pin "30") (pinfunction "30_30") (pintype "passive"))
    )
    (net (code "241") (name "unconnected-(J8-Pad1)") (class "Default")
      (node (ref "J8") (pin "1") (pinfunction "1_1") (pintype "passive"))
    )
    (net (code "242") (name "unconnected-(J8-Pad2)") (class "Default")
      (node (ref "J8") (pin "2") (pinfunction "2_2") (pintype "passive"))
    )
    (net (code "243") (name "unconnected-(J8-Pad3)") (class "Default")
      (node (ref "J8") (pin "3") (pinfunction "3_3") (pintype "passive"))
    )
    (net (code "244") (name "unconnected-(J8-Pad4)") (class "Default")
      (node (ref "J8") (pin "4") (pinfunction "4_4") (pintype "passive"))
    )
    (net (code "245") (name "unconnected-(J8-Pad5)") (class "Default")
      (node (ref "J8") (pin "5") (pinfunction "5_5") (pintype "passive"))
    )
    (net (code "246") (name "unconnected-(J8-Pad6)") (class "Default")
      (node (ref "J8") (pin "6") (pinfunction "6_6") (pintype "passive"))
    )
    (net (code "247") (name "unconnected-(J8-Pad7)") (class "Default")
      (node (ref "J8") (pin "7") (pinfunction "7_7") (pintype "passive"))
    )
    (net (code "248") (name "unconnected-(J8-Pad8)") (class "Default")
      (node (ref "J8") (pin "8") (pinfunction "8_8") (pintype "passive"))
    )
    (net (code "249") (name "unconnected-(J8-Pad9)") (class "Default")
      (node (ref "J8") (pin "9") (pinfunction "9_9") (pintype "passive"))
    )
    (net (code "250") (name "unconnected-(J8-Pad10)") (class "Default")
      (node (ref "J8") (pin "10") (pinfunction "10_10") (pintype "passive"))
    )
    (net (code "251") (name "unconnected-(J8-Pad11)") (class "Default")
      (node (ref "J8") (pin "11") (pinfunction "11_11") (pintype "passive"))
    )
    (net (code "252") (name "unconnected-(J8-Pad12)") (class "Default")
      (node (ref "J8") (pin "12") (pinfunction "12_12") (pintype "passive"))
    )
    (net (code "253") (name "unconnected-(J8-Pad13)") (class "Default")
      (node (ref "J8") (pin "13") (pinfunction "13_13") (pintype "passive"))
    )
    (net (code "254") (name "unconnected-(J8-Pad14)") (class "Default")
      (node (ref "J8") (pin "14") (pinfunction "14_14") (pintype "passive"))
    )
    (net (code "255") (name "unconnected-(J8-Pad15)") (class "Default")
      (node (ref "J8") (pin "15") (pinfunction "15_15") (pintype "passive"))
    )
    (net (code "256") (name "unconnected-(J8-Pad16)") (class "Default")
      (node (ref "J8") (pin "16") (pinfunction "16_16") (pintype "passive"))
    )
    (net (code "257") (name "unconnected-(J8-Pad17)") (class "Default")
      (node (ref "J8") (pin "17") (pinfunction "17_17") (pintype "passive"))
    )
    (net (code "258") (name "unconnected-(J8-Pad18)") (class "Default")
      (node (ref "J8") (pin "18") (pinfunction "18_18") (pintype "passive"))
    )
    (net (code "259") (name "unconnected-(J8-Pad19)") (class "Default")
      (node (ref "J8") (pin "19") (pinfunction "19_19") (pintype "passive"))
    )
    (net (code "260") (name "unconnected-(J8-Pad20)") (class "Default")
      (node (ref "J8") (pin "20") (pinfunction "20_20") (pintype "passive"))
    )
    (net (code "261") (name "unconnected-(J8-Pad21)") (class "Default")
      (node (ref "J8") (pin "21") (pinfunction "21_21") (pintype "passive"))
    )
    (net (code "262") (name "unconnected-(J8-Pad22)") (class "Default")
      (node (ref "J8") (pin "22") (pinfunction "22_22") (pintype "passive"))
    )
    (net (code "263") (name "unconnected-(J8-Pad23)") (class "Default")
      (node (ref "J8") (pin "23") (pinfunction "23_23") (pintype "passive"))
    )
    (net (code "264") (name "unconnected-(J8-Pad24)") (class "Default")
      (node (ref "J8") (pin "24") (pinfunction "24_24") (pintype "passive"))
    )
    (net (code "265") (name "unconnected-(J8-Pad25)") (class "Default")
      (node (ref "J8") (pin "25") (pinfunction "25_25") (pintype "passive"))
    )
    (net (code "266") (name "unconnected-(J8-Pad26)") (class "Default")
      (node (ref "J8") (pin "26") (pinfunction "26_26") (pintype "passive"))
    )
    (net (code "267") (name "unconnected-(J8-Pad27)") (class "Default")
      (node (ref "J8") (pin "27") (pinfunction "27_27") (pintype "passive"))
    )
    (net (code "268") (name "unconnected-(J8-Pad28)") (class "Default")
      (node (ref "J8") (pin "28") (pinfunction "28_28") (pintype "passive"))
    )
    (net (code "269") (name "unconnected-(J8-Pad29)") (class "Default")
      (node (ref "J8") (pin "29") (pinfunction "29_29") (pintype "passive"))
    )
    (net (code "270") (name "unconnected-(J8-Pad30)") (class "Default")
      (node (ref "J8") (pin "30") (pinfunction "30_30") (pintype "passive"))
    )
    (net (code "271") (name "unconnected-(J9-Pad1)") (class "Default")
      (node (ref "J9") (pin "1") (pinfunction "1_1") (pintype "passive"))
    )
    (net (code "272") (name "unconnected-(J9-Pad2)") (class "Default")
      (node (ref "J9") (pin "2") (pinfunction "2_2") (pintype "passive"))
    )
    (net (code "273") (name "unconnected-(J9-Pad3)") (class "Default")
      (node (ref "J9") (pin "3") (pinfunction "3_3") (pintype "passive"))
    )
    (net (code "274") (name "unconnected-(J9-Pad4)") (class "Default")
      (node (ref "J9") (pin "4") (pinfunction "4_4") (pintype "passive"))
    )
    (net (code "275") (name "unconnected-(J9-Pad5)") (class "Default")
      (node (ref "J9") (pin "5") (pinfunction "5_5") (pintype "passive"))
    )
    (net (code "276") (name "unconnected-(J9-Pad6)") (class "Default")
      (node (ref "J9") (pin "6") (pinfunction "6_6") (pintype "passive"))
    )
    (net (code "277") (name "unconnected-(J9-Pad7)") (class "Default")
      (node (ref "J9") (pin "7") (pinfunction "7_7") (pintype "passive"))
    )
    (net (code "278") (name "unconnected-(J9-Pad8)") (class "Default")
      (node (ref "J9") (pin "8") (pinfunction "8_8") (pintype "passive"))
    )
    (net (code "279") (name "unconnected-(J9-Pad9)") (class "Default")
      (node (ref "J9") (pin "9") (pinfunction "9_9") (pintype "passive"))
    )
    (net (code "280") (name "unconnected-(J9-Pad10)") (class "Default")
      (node (ref "J9") (pin "10") (pinfunction "10_10") (pintype "passive"))
    )
    (net (code "281") (name "unconnected-(J9-Pad11)") (class "Default")
      (node (ref "J9") (pin "11") (pinfunction "11_11") (pintype "passive"))
    )
    (net (code "282") (name "unconnected-(J9-Pad12)") (class "Default")
      (node (ref "J9") (pin "12") (pinfunction "12_12") (pintype "passive"))
    )
    (net (code "283") (name "unconnected-(J9-Pad13)") (class "Default")
      (node (ref "J9") (pin "13") (pinfunction "13_13") (pintype "passive"))
    )
    (net (code "284") (name "unconnected-(J9-Pad14)") (class "Default")
      (node (ref "J9") (pin "14") (pinfunction "14_14") (pintype "passive"))
    )
    (net (code "285") (name "unconnected-(J9-Pad15)") (class "Default")
      (node (ref "J9") (pin "15") (pinfunction "15_15") (pintype "passive"))
    )
    (net (code "286") (name "unconnected-(J9-Pad16)") (class "Default")
      (node (ref "J9") (pin "16") (pinfunction "16_16") (pintype "passive"))
    )
    (net (code "287") (name "unconnected-(J9-Pad17)") (class "Default")
      (node (ref "J9") (pin "17") (pinfunction "17_17") (pintype "passive"))
    )
    (net (code "288") (name "unconnected-(J9-Pad18)") (class "Default")
      (node (ref "J9") (pin "18") (pinfunction "18_18") (pintype "passive"))
    )
    (net (code "289") (name "unconnected-(J9-Pad19)") (class "Default")
      (node (ref "J9") (pin "19") (pinfunction "19_19") (pintype "passive"))
    )
    (net (code "290") (name "unconnected-(J9-Pad20)") (class "Default")
      (node (ref "J9") (pin "20") (pinfunction "20_20") (pintype "passive"))
    )
    (net (code "291") (name "unconnected-(J9-Pad21)") (class "Default")
      (node (ref "J9") (pin "21") (pinfunction "21_21") (pintype "passive"))
    )
    (net (code "292") (name "unconnected-(J9-Pad22)") (class "Default")
      (node (ref "J9") (pin "22") (pinfunction "22_22") (pintype "passive"))
    )
    (net (code "293") (name "unconnected-(J9-Pad23)") (class "Default")
      (node (ref "J9") (pin "23") (pinfunction "23_23") (pintype "passive"))
    )
    (net (code "294") (name "unconnected-(J9-Pad24)") (class "Default")
      (node (ref "J9") (pin "24") (pinfunction "24_24") (pintype "passive"))
    )
    (net (code "295") (name "unconnected-(J9-Pad25)") (class "Default")
      (node (ref "J9") (pin "25") (pinfunction "25_25") (pintype "passive"))
    )
    (net (code "296") (name "unconnected-(J9-Pad26)") (class "Default")
      (node (ref "J9") (pin "26") (pinfunction "26_26") (pintype "passive"))
    )
    (net (code "297") (name "unconnected-(J9-Pad27)") (class "Default")
      (node (ref "J9") (pin "27") (pinfunction "27_27") (pintype "passive"))
    )
    (net (code "298") (name "unconnected-(J9-Pad28)") (class "Default")
      (node (ref "J9") (pin "28") (pinfunction "28_28") (pintype "passive"))
    )
    (net (code "299") (name "unconnected-(J9-Pad29)") (class "Default")
      (node (ref "J9") (pin "29") (pinfunction "29_29") (pintype "passive"))
    )
    (net (code "300") (name "unconnected-(J9-Pad30)") (class "Default")
      (node (ref "J9") (pin "30") (pinfunction "30_30") (pintype "passive"))
    )
    (net (code "301") (name "unconnected-(J10-Pad1)") (class "Default")
      (node (ref "J10") (pin "1") (pinfunction "1_1") (pintype "passive"))
    )
    (net (code "302") (name "unconnected-(J10-Pad2)") (class "Default")
      (node (ref "J10") (pin "2") (pinfunction "2_2") (pintype "passive"))
    )
    (net (code "303") (name "unconnected-(J10-Pad3)") (class "Default")
      (node (ref "J10") (pin "3") (pinfunction "3_3") (pintype "passive"))
    )
    (net (code "304") (name "unconnected-(J10-Pad4)") (class "Default")
      (node (ref "J10") (pin "4") (pinfunction "4_4") (pintype "passive"))
    )
    (net (code "305") (name "unconnected-(J10-Pad5)") (class "Default")
      (node (ref "J10") (pin "5") (pinfunction "5_5") (pintype "passive"))
    )
    (net (code "306") (name "unconnected-(J10-Pad6)") (class "Default")
      (node (ref "J10") (pin "6") (pinfunction "6_6") (pintype "passive"))
    )
    (net (code "307") (name "unconnected-(J10-Pad7)") (class "Default")
      (node (ref "J10") (pin "7") (pinfunction "7_7") (pintype "passive"))
    )
    (net (code "308") (name "unconnected-(J10-Pad8)") (class "Default")
      (node (ref "J10") (pin "8") (pinfunction "8_8") (pintype "passive"))
    )
    (net (code "309") (name "unconnected-(J10-Pad9)") (class "Default")
      (node (ref "J10") (pin "9") (pinfunction "9_9") (pintype "passive"))
    )
    (net (code "310") (name "unconnected-(J10-Pad10)") (class "Default")
      (node (ref "J10") (pin "10") (pinfunction "10_10") (pintype "passive"))
    )
    (net (code "311") (name "unconnected-(J10-Pad11)") (class "Default")
      (node (ref "J10") (pin "11") (pinfunction "11_11") (pintype "passive"))
    )
    (net (code "312") (name "unconnected-(J10-Pad12)") (class "Default")
      (node (ref "J10") (pin "12") (pinfunction "12_12") (pintype "passive"))
    )
    (net (code "313") (name "unconnected-(J10-Pad13)") (class "Default")
      (node (ref "J10") (pin "13") (pinfunction "13_13") (pintype "passive"))
    )
    (net (code "314") (name "unconnected-(J10-Pad14)") (class "Default")
      (node (ref "J10") (pin "14") (pinfunction "14_14") (pintype "passive"))
    )
    (net (code "315") (name "unconnected-(J10-Pad15)") (class "Default")
      (node (ref "J10") (pin "15") (pinfunction "15_15") (pintype "passive"))
    )
    (net (code "316") (name "unconnected-(J10-Pad16)") (class "Default")
      (node (ref "J10") (pin "16") (pinfunction "16_16") (pintype "passive"))
    )
    (net (code "317") (name "unconnected-(J10-Pad17)") (class "Default")
      (node (ref "J10") (pin "17") (pinfunction "17_17") (pintype "passive"))
    )
    (net (code "318") (name "unconnected-(J10-Pad18)") (class "Default")
      (node (ref "J10") (pin "18") (pinfunction "18_18") (pintype "passive"))
    )
    (net (code "319") (name "unconnected-(J10-Pad19)") (class "Default")
      (node (ref "J10") (pin "19") (pinfunction "19_19") (pintype "passive"))
    )
    (net (code "320") (name "unconnected-(J10-Pad20)") (class "Default")
      (node (ref "J10") (pin "20") (pinfunction "20_20") (pintype "passive"))
    )
    (net (code "321") (name "unconnected-(J10-Pad21)") (class "Default")
      (node (ref "J10") (pin "21") (pinfunction "21_21") (pintype "passive"))
    )
    (net (code "322") (name "unconnected-(J10-Pad22)") (class "Default")
      (node (ref "J10") (pin "22") (pinfunction "22_22") (pintype "passive"))
    )
    (net (code "323") (name "unconnected-(J10-Pad23)") (class "Default")
      (node (ref "J10") (pin "23") (pinfunction "23_23") (pintype "passive"))
    )
    (net (code "324") (name "unconnected-(J10-Pad24)") (class "Default")
      (node (ref "J10") (pin "24") (pinfunction "24_24") (pintype "passive"))
    )
    (net (code "325") (name "unconnected-(J10-Pad25)") (class "Default")
      (node (ref "J10") (pin "25") (pinfunction "25_25") (pintype "passive"))
    )
    (net (code "326") (name "unconnected-(J10-Pad26)") (class "Default")
      (node (ref "J10") (pin "26") (pinfunction "26_26") (pintype "passive"))
    )
    (net (code "327") (name "unconnected-(J10-Pad27)") (class "Default")
      (node (ref "J10") (pin "27") (pinfunction "27_27") (pintype "passive"))
    )
    (net (code "328") (name "unconnected-(J10-Pad28)") (class "Default")
      (node (ref "J10") (pin "28") (pinfunction "28_28") (pintype "passive"))
    )
    (net (code "329") (name "unconnected-(J10-Pad29)") (class "Default")
      (node (ref "J10") (pin "29") (pinfunction "29_29") (pintype "passive"))
    )
    (net (code "330") (name "unconnected-(J10-Pad30)") (class "Default")
      (node (ref "J10") (pin "30") (pinfunction "30_30") (pintype "passive"))
    )
    (net (code "331") (name "unconnected-(J11-Pad1)") (class "Default")
      (node (ref "J11") (pin "1") (pinfunction "1_1") (pintype "passive"))
    )
    (net (code "332") (name "unconnected-(J11-Pad2)") (class "Default")
      (node (ref "J11") (pin "2") (pinfunction "2_2") (pintype "passive"))
    )
    (net (code "333") (name "unconnected-(J11-Pad3)") (class "Default")
      (node (ref "J11") (pin "3") (pinfunction "3_3") (pintype "passive"))
    )
    (net (code "334") (name "unconnected-(J11-Pad4)") (class "Default")
      (node (ref "J11") (pin "4") (pinfunction "4_4") (pintype "passive"))
    )
    (net (code "335") (name "unconnected-(J11-Pad5)") (class "Default")
      (node (ref "J11") (pin "5") (pinfunction "5_5") (pintype "passive"))
    )
    (net (code "336") (name "unconnected-(J11-Pad6)") (class "Default")
      (node (ref "J11") (pin "6") (pinfunction "6_6") (pintype "passive"))
    )
    (net (code "337") (name "unconnected-(J11-Pad7)") (class "Default")
      (node (ref "J11") (pin "7") (pinfunction "7_7") (pintype "passive"))
    )
    (net (code "338") (name "unconnected-(J11-Pad8)") (class "Default")
      (node (ref "J11") (pin "8") (pinfunction "8_8") (pintype "passive"))
    )
    (net (code "339") (name "unconnected-(J11-Pad9)") (class "Default")
      (node (ref "J11") (pin "9") (pinfunction "9_9") (pintype "passive"))
    )
    (net (code "340") (name "unconnected-(J11-Pad10)") (class "Default")
      (node (ref "J11") (pin "10") (pinfunction "10_10") (pintype "passive"))
    )
    (net (code "341") (name "unconnected-(J11-Pad11)") (class "Default")
      (node (ref "J11") (pin "11") (pinfunction "11_11") (pintype "passive"))
    )
    (net (code "342") (name "unconnected-(J11-Pad12)") (class "Default")
      (node (ref "J11") (pin "12") (pinfunction "12_12") (pintype "passive"))
    )
    (net (code "343") (name "unconnected-(J11-Pad13)") (class "Default")
      (node (ref "J11") (pin "13") (pinfunction "13_13") (pintype "passive"))
    )
    (net (code "344") (name "unconnected-(J11-Pad14)") (class "Default")
      (node (ref "J11") (pin "14") (pinfunction "14_14") (pintype "passive"))
    )
    (net (code "345") (name "unconnected-(J11-Pad15)") (class "Default")
      (node (ref "J11") (pin "15") (pinfunction "15_15") (pintype "passive"))
    )
    (net (code "346") (name "unconnected-(J11-Pad16)") (class "Default")
      (node (ref "J11") (pin "16") (pinfunction "16_16") (pintype "passive"))
    )
    (net (code "347") (name "unconnected-(J11-Pad17)") (class "Default")
      (node (ref "J11") (pin "17") (pinfunction "17_17") (pintype "passive"))
    )
    (net (code "348") (name "unconnected-(J11-Pad18)") (class "Default")
      (node (ref "J11") (pin "18") (pinfunction "18_18") (pintype "passive"))
    )
    (net (code "349") (name "unconnected-(J11-Pad19)") (class "Default")
      (node (ref "J11") (pin "19") (pinfunction "19_19") (pintype "passive"))
    )
    (net (code "350") (name "unconnected-(J11-Pad20)") (class "Default")
      (node (ref "J11") (pin "20") (pinfunction "20_20") (pintype "passive"))
    )
    (net (code "351") (name "unconnected-(J11-Pad21)") (class "Default")
      (node (ref "J11") (pin "21") (pinfunction "21_21") (pintype "passive"))
    )
    (net (code "352") (name "unconnected-(J11-Pad22)") (class "Default")
      (node (ref "J11") (pin "22") (pinfunction "22_22") (pintype "passive"))
    )
    (net (code "353") (name "unconnected-(J11-Pad23)") (class "Default")
      (node (ref "J11") (pin "23") (pinfunction "23_23") (pintype "passive"))
    )
    (net (code "354") (name "unconnected-(J11-Pad24)") (class "Default")
      (node (ref "J11") (pin "24") (pinfunction "24_24") (pintype "passive"))
    )
    (net (code "355") (name "unconnected-(J11-Pad25)") (class "Default")
      (node (ref "J11") (pin "25") (pinfunction "25_25") (pintype "passive"))
    )
    (net (code "356") (name "unconnected-(J11-Pad26)") (class "Default")
      (node (ref "J11") (pin "26") (pinfunction "26_26") (pintype "passive"))
    )
    (net (code "357") (name "unconnected-(J11-Pad27)") (class "Default")
      (node (ref "J11") (pin "27") (pinfunction "27_27") (pintype "passive"))
    )
    (net (code "358") (name "unconnected-(J11-Pad28)") (class "Default")
      (node (ref "J11") (pin "28") (pinfunction "28_28") (pintype "passive"))
    )
    (net (code "359") (name "unconnected-(J11-Pad29)") (class "Default")
      (node (ref "J11") (pin "29") (pinfunction "29_29") (pintype "passive"))
    )
    (net (code "360") (name "unconnected-(J11-Pad30)") (class "Default")
      (node (ref "J11") (pin "30") (pinfunction "30_30") (pintype "passive"))
    )
    (net (code "361") (name "unconnected-(J12-Pad1)") (class "Default")
      (node (ref "J12") (pin "1") (pinfunction "1_1") (pintype "passive"))
    )
    (net (code "362") (name "unconnected-(J12-Pad2)") (class "Default")
      (node (ref "J12") (pin "2") (pinfunction "2_2") (pintype "passive"))
    )
    (net (code "363") (name "unconnected-(J12-Pad3)") (class "Default")
      (node (ref "J12") (pin "3") (pinfunction "3_3") (pintype "passive"))
    )
    (net (code "364") (name "unconnected-(J12-Pad4)") (class "Default")
      (node (ref "J12") (pin "4") (pinfunction "4_4") (pintype "passive"))
    )
    (net (code "365") (name "unconnected-(J12-Pad5)") (class "Default")
      (node (ref "J12") (pin "5") (pinfunction "5_5") (pintype "passive"))
    )
    (net (code "366") (name "unconnected-(J12-Pad6)") (class "Default")
      (node (ref "J12") (pin "6") (pinfunction "6_6") (pintype "passive"))
    )
    (net (code "367") (name "unconnected-(J12-Pad7)") (class "Default")
      (node (ref "J12") (pin "7") (pinfunction "7_7") (pintype "passive"))
    )
    (net (code "368") (name "unconnected-(J12-Pad8)") (class "Default")
      (node (ref "J12") (pin "8") (pinfunction "8_8") (pintype "passive"))
    )
    (net (code "369") (name "unconnected-(J12-Pad9)") (class "Default")
      (node (ref "J12") (pin "9") (pinfunction "9_9") (pintype "passive"))
    )
    (net (code "370") (name "unconnected-(J12-Pad10)") (class "Default")
      (node (ref "J12") (pin "10") (pinfunction "10_10") (pintype "passive"))
    )
    (net (code "371") (name "unconnected-(J12-Pad11)") (class "Default")
      (node (ref "J12") (pin "11") (pinfunction "11_11") (pintype "passive"))
    )
    (net (code "372") (name "unconnected-(J12-Pad12)") (class "Default")
      (node (ref "J12") (pin "12") (pinfunction "12_12") (pintype "passive"))
    )
    (net (code "373") (name "unconnected-(J12-Pad13)") (class "Default")
      (node (ref "J12") (pin "13") (pinfunction "13_13") (pintype "passive"))
    )
    (net (code "374") (name "unconnected-(J12-Pad14)") (class "Default")
      (node (ref "J12") (pin "14") (pinfunction "14_14") (pintype "passive"))
    )
    (net (code "375") (name "unconnected-(J12-Pad15)") (class "Default")
      (node (ref "J12") (pin "15") (pinfunction "15_15") (pintype "passive"))
    )
    (net (code "376") (name "unconnected-(J12-Pad16)") (class "Default")
      (node (ref "J12") (pin "16") (pinfunction "16_16") (pintype "passive"))
    )
    (net (code "377") (name "unconnected-(J12-Pad17)") (class "Default")
      (node (ref "J12") (pin "17") (pinfunction "17_17") (pintype "passive"))
    )
    (net (code "378") (name "unconnected-(J12-Pad18)") (class "Default")
      (node (ref "J12") (pin "18") (pinfunction "18_18") (pintype "passive"))
    )
    (net (code "379") (name "unconnected-(J12-Pad19)") (class "Default")
      (node (ref "J12") (pin "19") (pinfunction "19_19") (pintype "passive"))
    )
    (net (code "380") (name "unconnected-(J12-Pad20)") (class "Default")
      (node (ref "J12") (pin "20") (pinfunction "20_20") (pintype "passive"))
    )
    (net (code "381") (name "unconnected-(J12-Pad21)") (class "Default")
      (node (ref "J12") (pin "21") (pinfunction "21_21") (pintype "passive"))
    )
    (net (code "382") (name "unconnected-(J12-Pad22)") (class "Default")
      (node (ref "J12") (pin "22") (pinfunction "22_22") (pintype "passive"))
    )
    (net (code "383") (name "unconnected-(J12-Pad23)") (class "Default")
      (node (ref "J12") (pin "23") (pinfunction "23_23") (pintype "passive"))
    )
    (net (code "384") (name "unconnected-(J12-Pad24)") (class "Default")
      (node (ref "J12") (pin "24") (pinfunction "24_24") (pintype "passive"))
    )
    (net (code "385") (name "unconnected-(J12-Pad25)") (class "Default")
      (node (ref "J12") (pin "25") (pinfunction "25_25") (pintype "passive"))
    )
    (net (code "386") (name "unconnected-(J12-Pad26)") (class "Default")
      (node (ref "J12") (pin "26") (pinfunction "26_26") (pintype "passive"))
    )
    (net (code "387") (name "unconnected-(J12-Pad27)") (class "Default")
      (node (ref "J12") (pin "27") (pinfunction "27_27") (pintype "passive"))
    )
    (net (code "388") (name "unconnected-(J12-Pad28)") (class "Default")
      (node (ref "J12") (pin "28") (pinfunction "28_28") (pintype "passive"))
    )
    (net (code "389") (name "unconnected-(J12-Pad29)") (class "Default")
      (node (ref "J12") (pin "29") (pinfunction "29_29") (pintype "passive"))
    )
    (net (code "390") (name "unconnected-(J12-Pad30)") (class "Default")
      (node (ref "J12") (pin "30") (pinfunction "30_30") (pintype "passive"))
    )
    (net (code "391") (name "unconnected-(J13-Pad1)") (class "Default")
      (node (ref "J13") (pin "1") (pinfunction "1_1") (pintype "passive"))
    )
    (net (code "392") (name "unconnected-(J13-Pad2)") (class "Default")
      (node (ref "J13") (pin "2") (pinfunction "2_2") (pintype "passive"))
    )
    (net (code "393") (name "unconnected-(J13-Pad3)") (class "Default")
      (node (ref "J13") (pin "3") (pinfunction "3_3") (pintype "passive"))
    )
    (net (code "394") (name "unconnected-(J13-Pad4)") (class "Default")
      (node (ref "J13") (pin "4") (pinfunction "4_4") (pintype "passive"))
    )
    (net (code "395") (name "unconnected-(J13-Pad5)") (class "Default")
      (node (ref "J13") (pin "5") (pinfunction "5_5") (pintype "passive"))
    )
    (net (code "396") (name "unconnected-(J13-Pad6)") (class "Default")
      (node (ref "J13") (pin "6") (pinfunction "6_6") (pintype "passive"))
    )
    (net (code "397") (name "unconnected-(J13-Pad7)") (class "Default")
      (node (ref "J13") (pin "7") (pinfunction "7_7") (pintype "passive"))
    )
    (net (code "398") (name "unconnected-(J13-Pad8)") (class "Default")
      (node (ref "J13") (pin "8") (pinfunction "8_8") (pintype "passive"))
    )
    (net (code "399") (name "unconnected-(J13-Pad9)") (class "Default")
      (node (ref "J13") (pin "9") (pinfunction "9_9") (pintype "passive"))
    )
    (net (code "400") (name "unconnected-(J13-Pad10)") (class "Default")
      (node (ref "J13") (pin "10") (pinfunction "10_10") (pintype "passive"))
    )
    (net (code "401") (name "unconnected-(J13-Pad11)") (class "Default")
      (node (ref "J13") (pin "11") (pinfunction "11_11") (pintype "passive"))
    )
    (net (code "402") (name "unconnected-(J13-Pad12)") (class "Default")
      (node (ref "J13") (pin "12") (pinfunction "12_12") (pintype "passive"))
    )
    (net (code "403") (name "unconnected-(J13-Pad13)") (class "Default")
      (node (ref "J13") (pin "13") (pinfunction "13_13") (pintype "passive"))
    )
    (net (code "404") (name "unconnected-(J13-Pad14)") (class "Default")
      (node (ref "J13") (pin "14") (pinfunction "14_14") (pintype "passive"))
    )
    (net (code "405") (name "unconnected-(J13-Pad15)") (class "Default")
      (node (ref "J13") (pin "15") (pinfunction "15_15") (pintype "passive"))
    )
    (net (code "406") (name "unconnected-(J13-Pad16)") (class "Default")
      (node (ref "J13") (pin "16") (pinfunction "16_16") (pintype "passive"))
    )
    (net (code "407") (name "unconnected-(J13-Pad17)") (class "Default")
      (node (ref "J13") (pin "17") (pinfunction "17_17") (pintype "passive"))
    )
    (net (code "408") (name "unconnected-(J13-Pad18)") (class "Default")
      (node (ref "J13") (pin "18") (pinfunction "18_18") (pintype "passive"))
    )
    (net (code "409") (name "unconnected-(J13-Pad19)") (class "Default")
      (node (ref "J13") (pin "19") (pinfunction "19_19") (pintype "passive"))
    )
    (net (code "410") (name "unconnected-(J13-Pad20)") (class "Default")
      (node (ref "J13") (pin "20") (pinfunction "20_20") (pintype "passive"))
    )
    (net (code "411") (name "unconnected-(J13-Pad21)") (class "Default")
      (node (ref "J13") (pin "21") (pinfunction "21_21") (pintype "passive"))
    )
    (net (code "412") (name "unconnected-(J13-Pad22)") (class "Default")
      (node (ref "J13") (pin "22") (pinfunction "22_22") (pintype "passive"))
    )
    (net (code "413") (name "unconnected-(J13-Pad23)") (class "Default")
      (node (ref "J13") (pin "23") (pinfunction "23_23") (pintype "passive"))
    )
    (net (code "414") (name "unconnected-(J13-Pad24)") (class "Default")
      (node (ref "J13") (pin "24") (pinfunction "24_24") (pintype "passive"))
    )
    (net (code "415") (name "unconnected-(J13-Pad25)") (class "Default")
      (node (ref "J13") (pin "25") (pinfunction "25_25") (pintype "passive"))
    )
    (net (code "416") (name "unconnected-(J13-Pad26)") (class "Default")
      (node (ref "J13") (pin "26") (pinfunction "26_26") (pintype "passive"))
    )
    (net (code "417") (name "unconnected-(J13-Pad27)") (class "Default")
      (node (ref "J13") (pin "27") (pinfunction "27_27") (pintype "passive"))
    )
    (net (code "418") (name "unconnected-(J13-Pad28)") (class "Default")
      (node (ref "J13") (pin "28") (pinfunction "28_28") (pintype "passive"))
    )
    (net (code "419") (name "unconnected-(J13-Pad29)") (class "Default")
      (node (ref "J13") (pin "29") (pinfunction "29_29") (pintype "passive"))
    )
    (net (code "420") (name "unconnected-(J13-Pad30)") (class "Default")
      (node (ref "J13") (pin "30") (pinfunction "30_30") (pintype "passive"))
    )
    (net (code "421") (name "unconnected-(J14-Pad1)") (class "Default")
      (node (ref "J14") (pin "1") (pinfunction "1_1") (pintype "passive"))
    )
    (net (code "422") (name "unconnected-(J14-Pad2)") (class "Default")
      (node (ref "J14") (pin "2") (pinfunction "2_2") (pintype "passive"))
    )
    (net (code "423") (name "unconnected-(J14-Pad3)") (class "Default")
      (node (ref "J14") (pin "3") (pinfunction "3_3") (pintype "passive"))
    )
    (net (code "424") (name "unconnected-(J14-Pad4)") (class "Default")
      (node (ref "J14") (pin "4") (pinfunction "4_4") (pintype "passive"))
    )
    (net (code "425") (name "unconnected-(J14-Pad5)") (class "Default")
      (node (ref "J14") (pin "5") (pinfunction "5_5") (pintype "passive"))
    )
    (net (code "426") (name "unconnected-(J14-Pad6)") (class "Default")
      (node (ref "J14") (pin "6") (pinfunction "6_6") (pintype "passive"))
    )
    (net (code "427") (name "unconnected-(J14-Pad7)") (class "Default")
      (node (ref "J14") (pin "7") (pinfunction "7_7") (pintype "passive"))
    )
    (net (code "428") (name "unconnected-(J14-Pad8)") (class "Default")
      (node (ref "J14") (pin "8") (pinfunction "8_8") (pintype "passive"))
    )
    (net (code "429") (name "unconnected-(J14-Pad9)") (class "Default")
      (node (ref "J14") (pin "9") (pinfunction "9_9") (pintype "passive"))
    )
    (net (code "430") (name "unconnected-(J14-Pad10)") (class "Default")
      (node (ref "J14") (pin "10") (pinfunction "10_10") (pintype "passive"))
    )
    (net (code "431") (name "unconnected-(J14-Pad11)") (class "Default")
      (node (ref "J14") (pin "11") (pinfunction "11_11") (pintype "passive"))
    )
    (net (code "432") (name "unconnected-(J14-Pad12)") (class "Default")
      (node (ref "J14") (pin "12") (pinfunction "12_12") (pintype "passive"))
    )
    (net (code "433") (name "unconnected-(J14-Pad13)") (class "Default")
      (node (ref "J14") (pin "13") (pinfunction "13_13") (pintype "passive"))
    )
    (net (code "434") (name "unconnected-(J14-Pad14)") (class "Default")
      (node (ref "J14") (pin "14") (pinfunction "14_14") (pintype "passive"))
    )
    (net (code "435") (name "unconnected-(J14-Pad15)") (class "Default")
      (node (ref "J14") (pin "15") (pinfunction "15_15") (pintype "passive"))
    )
    (net (code "436") (name "unconnected-(J14-Pad16)") (class "Default")
      (node (ref "J14") (pin "16") (pinfunction "16_16") (pintype "passive"))
    )
    (net (code "437") (name "unconnected-(J14-Pad17)") (class "Default")
      (node (ref "J14") (pin "17") (pinfunction "17_17") (pintype "passive"))
    )
    (net (code "438") (name "unconnected-(J14-Pad18)") (class "Default")
      (node (ref "J14") (pin "18") (pinfunction "18_18") (pintype "passive"))
    )
    (net (code "439") (name "unconnected-(J14-Pad19)") (class "Default")
      (node (ref "J14") (pin "19") (pinfunction "19_19") (pintype "passive"))
    )
    (net (code "440") (name "unconnected-(J14-Pad20)") (class "Default")
      (node (ref "J14") (pin "20") (pinfunction "20_20") (pintype "passive"))
    )
    (net (code "441") (name "unconnected-(J14-Pad21)") (class "Default")
      (node (ref "J14") (pin "21") (pinfunction "21_21") (pintype "passive"))
    )
    (net (code "442") (name "unconnected-(J14-Pad22)") (class "Default")
      (node (ref "J14") (pin "22") (pinfunction "22_22") (pintype "passive"))
    )
    (net (code "443") (name "unconnected-(J14-Pad23)") (class "Default")
      (node (ref "J14") (pin "23") (pinfunction "23_23") (pintype "passive"))
    )
    (net (code "444") (name "unconnected-(J14-Pad24)") (class "Default")
      (node (ref "J14") (pin "24") (pinfunction "24_24") (pintype "passive"))
    )
    (net (code "445") (name "unconnected-(J14-Pad25)") (class "Default")
      (node (ref "J14") (pin "25") (pinfunction "25_25") (pintype "passive"))
    )
    (net (code "446") (name "unconnected-(J14-Pad26)") (class "Default")
      (node (ref "J14") (pin "26") (pinfunction "26_26") (pintype "passive"))
    )
    (net (code "447") (name "unconnected-(J14-Pad27)") (class "Default")
      (node (ref "J14") (pin "27") (pinfunction "27_27") (pintype "passive"))
    )
    (net (code "448") (name "unconnected-(J14-Pad28)") (class "Default")
      (node (ref "J14") (pin "28") (pinfunction "28_28") (pintype "passive"))
    )
    (net (code "449") (name "unconnected-(J14-Pad29)") (class "Default")
      (node (ref "J14") (pin "29") (pinfunction "29_29") (pintype "passive"))
    )
    (net (code "450") (name "unconnected-(J14-Pad30)") (class "Default")
      (node (ref "J14") (pin "30") (pinfunction "30_30") (pintype "passive"))
    )
    (net (code "451") (name "unconnected-(J15-Pad1)") (class "Default")
      (node (ref "J15") (pin "1") (pinfunction "1_1") (pintype "passive"))
    )
    (net (code "452") (name "unconnected-(J15-Pad2)") (class "Default")
      (node (ref "J15") (pin "2") (pinfunction "2_2") (pintype "passive"))
    )
    (net (code "453") (name "unconnected-(J15-Pad3)") (class "Default")
      (node (ref "J15") (pin "3") (pinfunction "3_3") (pintype "passive"))
    )
    (net (code "454") (name "unconnected-(J15-Pad4)") (class "Default")
      (node (ref "J15") (pin "4") (pinfunction "4_4") (pintype "passive"))
    )
    (net (code "455") (name "unconnected-(J15-Pad5)") (class "Default")
      (node (ref "J15") (pin "5") (pinfunction "5_5") (pintype "passive"))
    )
    (net (code "456") (name "unconnected-(J15-Pad6)") (class "Default")
      (node (ref "J15") (pin "6") (pinfunction "6_6") (pintype "passive"))
    )
    (net (code "457") (name "unconnected-(J15-Pad7)") (class "Default")
      (node (ref "J15") (pin "7") (pinfunction "7_7") (pintype "passive"))
    )
    (net (code "458") (name "unconnected-(J15-Pad8)") (class "Default")
      (node (ref "J15") (pin "8") (pinfunction "8_8") (pintype "passive"))
    )
    (net (code "459") (name "unconnected-(J15-Pad9)") (class "Default")
      (node (ref "J15") (pin "9") (pinfunction "9_9") (pintype "passive"))
    )
    (net (code "460") (name "unconnected-(J15-Pad10)") (class "Default")
      (node (ref "J15") (pin "10") (pinfunction "10_10") (pintype "passive"))
    )
    (net (code "461") (name "unconnected-(J15-Pad11)") (class "Default")
      (node (ref "J15") (pin "11") (pinfunction "11_11") (pintype "passive"))
    )
    (net (code "462") (name "unconnected-(J15-Pad12)") (class "Default")
      (node (ref "J15") (pin "12") (pinfunction "12_12") (pintype "passive"))
    )
    (net (code "463") (name "unconnected-(J15-Pad13)") (class "Default")
      (node (ref "J15") (pin "13") (pinfunction "13_13") (pintype "passive"))
    )
    (net (code "464") (name "unconnected-(J15-Pad14)") (class "Default")
      (node (ref "J15") (pin "14") (pinfunction "14_14") (pintype "passive"))
    )
    (net (code "465") (name "unconnected-(J15-Pad15)") (class "Default")
      (node (ref "J15") (pin "15") (pinfunction "15_15") (pintype "passive"))
    )
    (net (code "466") (name "unconnected-(J15-Pad16)") (class "Default")
      (node (ref "J15") (pin "16") (pinfunction "16_16") (pintype "passive"))
    )
    (net (code "467") (name "unconnected-(J15-Pad17)") (class "Default")
      (node (ref "J15") (pin "17") (pinfunction "17_17") (pintype "passive"))
    )
    (net (code "468") (name "unconnected-(J15-Pad18)") (class "Default")
      (node (ref "J15") (pin "18") (pinfunction "18_18") (pintype "passive"))
    )
    (net (code "469") (name "unconnected-(J15-Pad19)") (class "Default")
      (node (ref "J15") (pin "19") (pinfunction "19_19") (pintype "passive"))
    )
    (net (code "470") (name "unconnected-(J15-Pad20)") (class "Default")
      (node (ref "J15") (pin "20") (pinfunction "20_20") (pintype "passive"))
    )
    (net (code "471") (name "unconnected-(J15-Pad21)") (class "Default")
      (node (ref "J15") (pin "21") (pinfunction "21_21") (pintype "passive"))
    )
    (net (code "472") (name "unconnected-(J15-Pad22)") (class "Default")
      (node (ref "J15") (pin "22") (pinfunction "22_22") (pintype "passive"))
    )
    (net (code "473") (name "unconnected-(J15-Pad23)") (class "Default")
      (node (ref "J15") (pin "23") (pinfunction "23_23") (pintype "passive"))
    )
    (net (code "474") (name "unconnected-(J15-Pad24)") (class "Default")
      (node (ref "J15") (pin "24") (pinfunction "24_24") (pintype "passive"))
    )
    (net (code "475") (name "unconnected-(J15-Pad25)") (class "Default")
      (node (ref "J15") (pin "25") (pinfunction "25_25") (pintype "passive"))
    )
    (net (code "476") (name "unconnected-(J15-Pad26)") (class "Default")
      (node (ref "J15") (pin "26") (pinfunction "26_26") (pintype "passive"))
    )
    (net (code "477") (name "unconnected-(J15-Pad27)") (class "Default")
      (node (ref "J15") (pin "27") (pinfunction "27_27") (pintype "passive"))
    )
    (net (code "478") (name "unconnected-(J15-Pad28)") (class "Default")
      (node (ref "J15") (pin "28") (pinfunction "28_28") (pintype "passive"))
    )
    (net (code "479") (name "unconnected-(J15-Pad29)") (class "Default")
      (node (ref "J15") (pin "29") (pinfunction "29_29") (pintype "passive"))
    )
    (net (code "480") (name "unconnected-(J15-Pad30)") (class "Default")
      (node (ref "J15") (pin "30") (pinfunction "30_30") (pintype "passive"))
    )
    (net (code "481") (name "unconnected-(J16-Pad1)") (class "Default")
      (node (ref "J16") (pin "1") (pinfunction "1_1") (pintype "passive"))
    )
    (net (code "482") (name "unconnected-(J16-Pad2)") (class "Default")
      (node (ref "J16") (pin "2") (pinfunction "2_2") (pintype "passive"))
    )
    (net (code "483") (name "unconnected-(J16-Pad3)") (class "Default")
      (node (ref "J16") (pin "3") (pinfunction "3_3") (pintype "passive"))
    )
    (net (code "484") (name "unconnected-(J16-Pad4)") (class "Default")
      (node (ref "J16") (pin "4") (pinfunction "4_4") (pintype "passive"))
    )
    (net (code "485") (name "unconnected-(J16-Pad5)") (class "Default")
      (node (ref "J16") (pin "5") (pinfunction "5_5") (pintype "passive"))
    )
    (net (code "486") (name "unconnected-(J16-Pad6)") (class "Default")
      (node (ref "J16") (pin "6") (pinfunction "6_6") (pintype "passive"))
    )
    (net (code "487") (name "unconnected-(J16-Pad7)") (class "Default")
      (node (ref "J16") (pin "7") (pinfunction "7_7") (pintype "passive"))
    )
    (net (code "488") (name "unconnected-(J16-Pad8)") (class "Default")
      (node (ref "J16") (pin "8") (pinfunction "8_8") (pintype "passive"))
    )
    (net (code "489") (name "unconnected-(J16-Pad9)") (class "Default")
      (node (ref "J16") (pin "9") (pinfunction "9_9") (pintype "passive"))
    )
    (net (code "490") (name "unconnected-(J16-Pad10)") (class "Default")
      (node (ref "J16") (pin "10") (pinfunction "10_10") (pintype "passive"))
    )
    (net (code "491") (name "unconnected-(J16-Pad11)") (class "Default")
      (node (ref "J16") (pin "11") (pinfunction "11_11") (pintype "passive"))
    )
    (net (code "492") (name "unconnected-(J16-Pad12)") (class "Default")
      (node (ref "J16") (pin "12") (pinfunction "12_12") (pintype "passive"))
    )
    (net (code "493") (name "unconnected-(J16-Pad13)") (class "Default")
      (node (ref "J16") (pin "13") (pinfunction "13_13") (pintype "passive"))
    )
    (net (code "494") (name "unconnected-(J16-Pad14)") (class "Default")
      (node (ref "J16") (pin "14") (pinfunction "14_14") (pintype "passive"))
    )
    (net (code "495") (name "unconnected-(J16-Pad15)") (class "Default")
      (node (ref "J16") (pin "15") (pinfunction "15_15") (pintype "passive"))
    )
    (net (code "496") (name "unconnected-(J16-Pad16)") (class "Default")
      (node (ref "J16") (pin "16") (pinfunction "16_16") (pintype "passive"))
    )
    (net (code "497") (name "unconnected-(J16-Pad17)") (class "Default")
      (node (ref "J16") (pin "17") (pinfunction "17_17") (pintype "passive"))
    )
    (net (code "498") (name "unconnected-(J16-Pad18)") (class "Default")
      (node (ref "J16") (pin "18") (pinfunction "18_18") (pintype "passive"))
    )
    (net (code "499") (name "unconnected-(J16-Pad19)") (class "Default")
      (node (ref "J16") (pin "19") (pinfunction "19_19") (pintype "passive"))
    )
    (net (code "500") (name "unconnected-(J16-Pad20)") (class "Default")
      (node (ref "J16") (pin "20") (pinfunction "20_20") (pintype "passive"))
    )
    (net (code "501") (name "unconnected-(J16-Pad21)") (class "Default")
      (node (ref "J16") (pin "21") (pinfunction "21_21") (pintype "passive"))
    )
    (net (code "502") (name "unconnected-(J16-Pad22)") (class "Default")
      (node (ref "J16") (pin "22") (pinfunction "22_22") (pintype "passive"))
    )
    (net (code "503") (name "unconnected-(J16-Pad23)") (class "Default")
      (node (ref "J16") (pin "23") (pinfunction "23_23") (pintype "passive"))
    )
    (net (code "504") (name "unconnected-(J16-Pad24)") (class "Default")
      (node (ref "J16") (pin "24") (pinfunction "24_24") (pintype "passive"))
    )
    (net (code "505") (name "unconnected-(J16-Pad25)") (class "Default")
      (node (ref "J16") (pin "25") (pinfunction "25_25") (pintype "passive"))
    )
    (net (code "506") (name "unconnected-(J16-Pad26)") (class "Default")
      (node (ref "J16") (pin "26") (pinfunction "26_26") (pintype "passive"))
    )
    (net (code "507") (name "unconnected-(J16-Pad27)") (class "Default")
      (node (ref "J16") (pin "27") (pinfunction "27_27") (pintype "passive"))
    )
    (net (code "508") (name "unconnected-(J16-Pad28)") (class "Default")
      (node (ref "J16") (pin "28") (pinfunction "28_28") (pintype "passive"))
    )
    (net (code "509") (name "unconnected-(J16-Pad29)") (class "Default")
      (node (ref "J16") (pin "29") (pinfunction "29_29") (pintype "passive"))
    )
    (net (code "510") (name "unconnected-(J16-Pad30)") (class "Default")
      (node (ref "J16") (pin "30") (pinfunction "30_30") (pintype "passive"))
    )
  )
)
